# SolarPanel_2p2AZ1.net
KiCad netlist of a schematic drawn in EAGLE
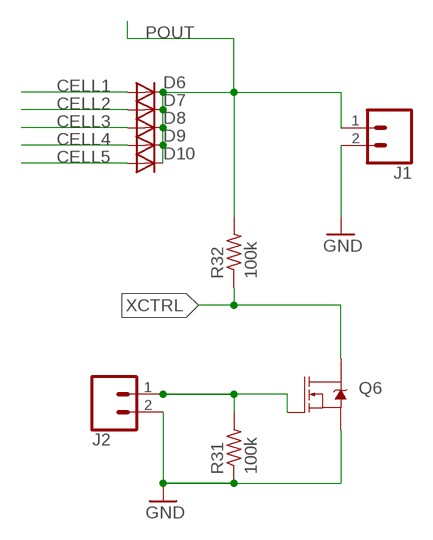
[diagram p0: schematic, sheet 1]
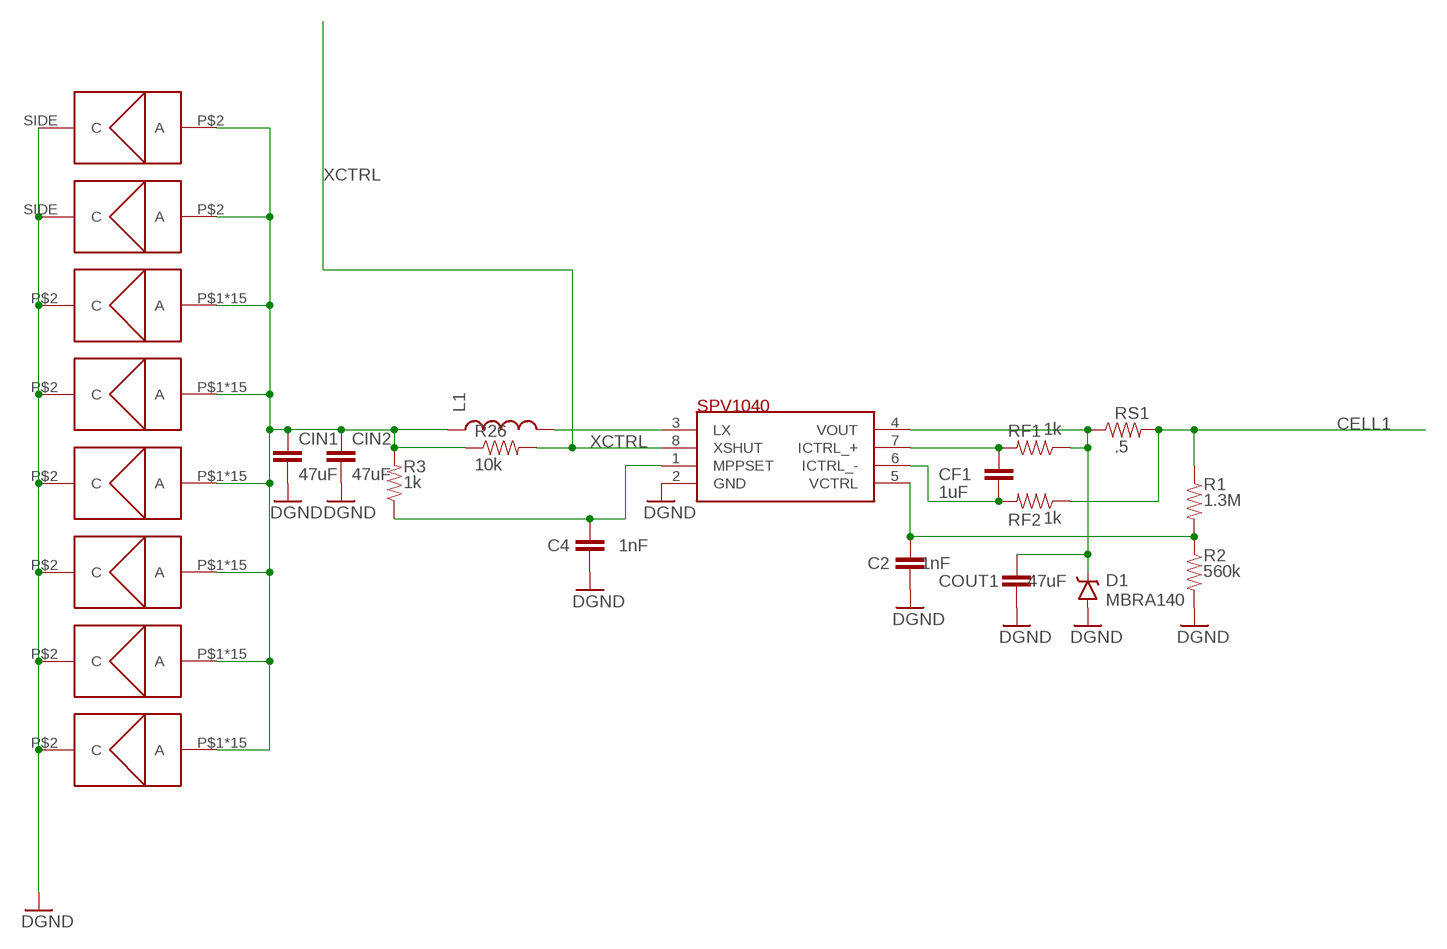
[diagram p1: schematic, sheet 2]
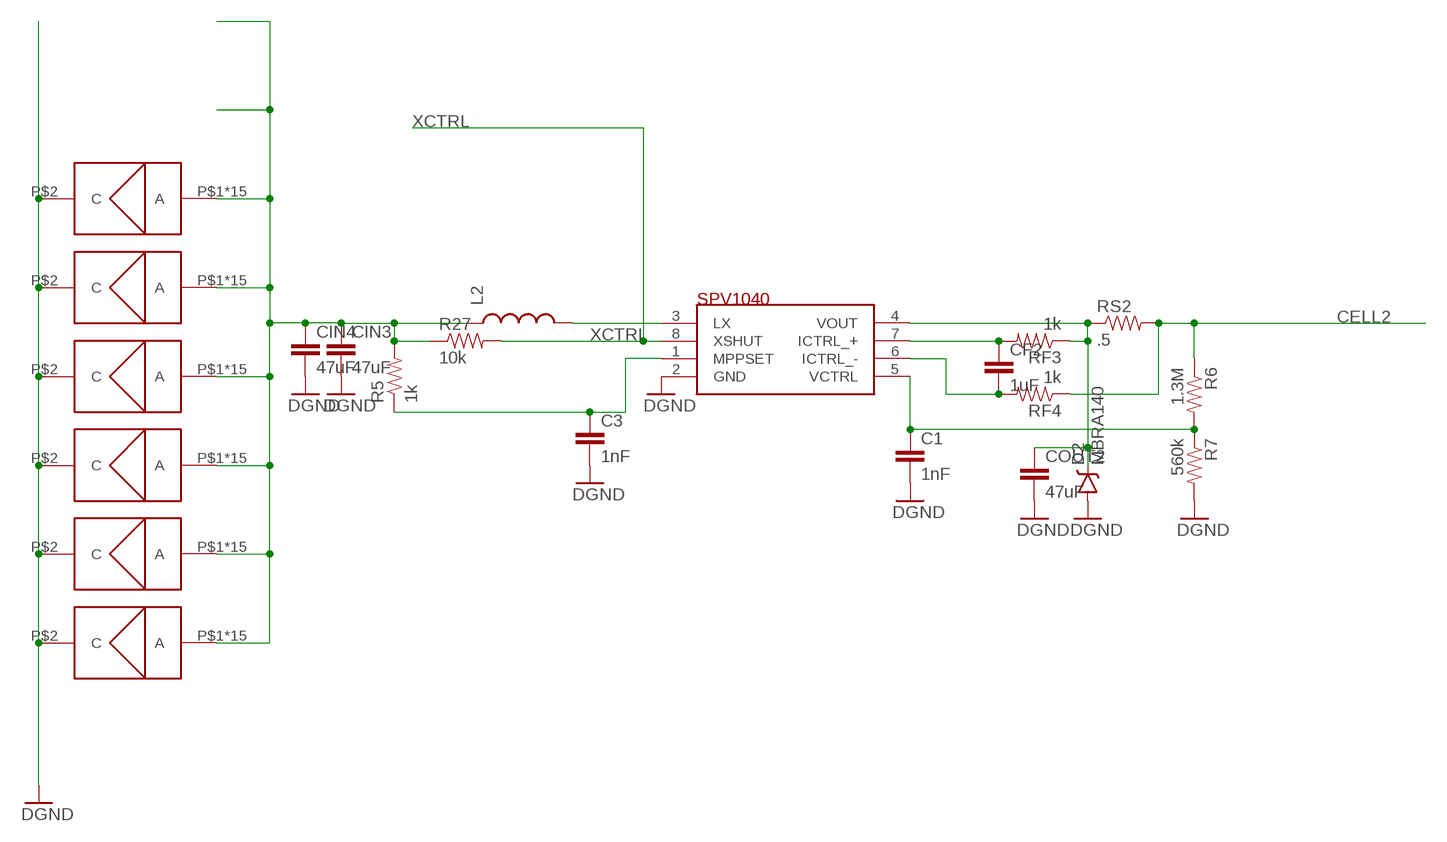
[diagram p2: schematic, sheet 3]
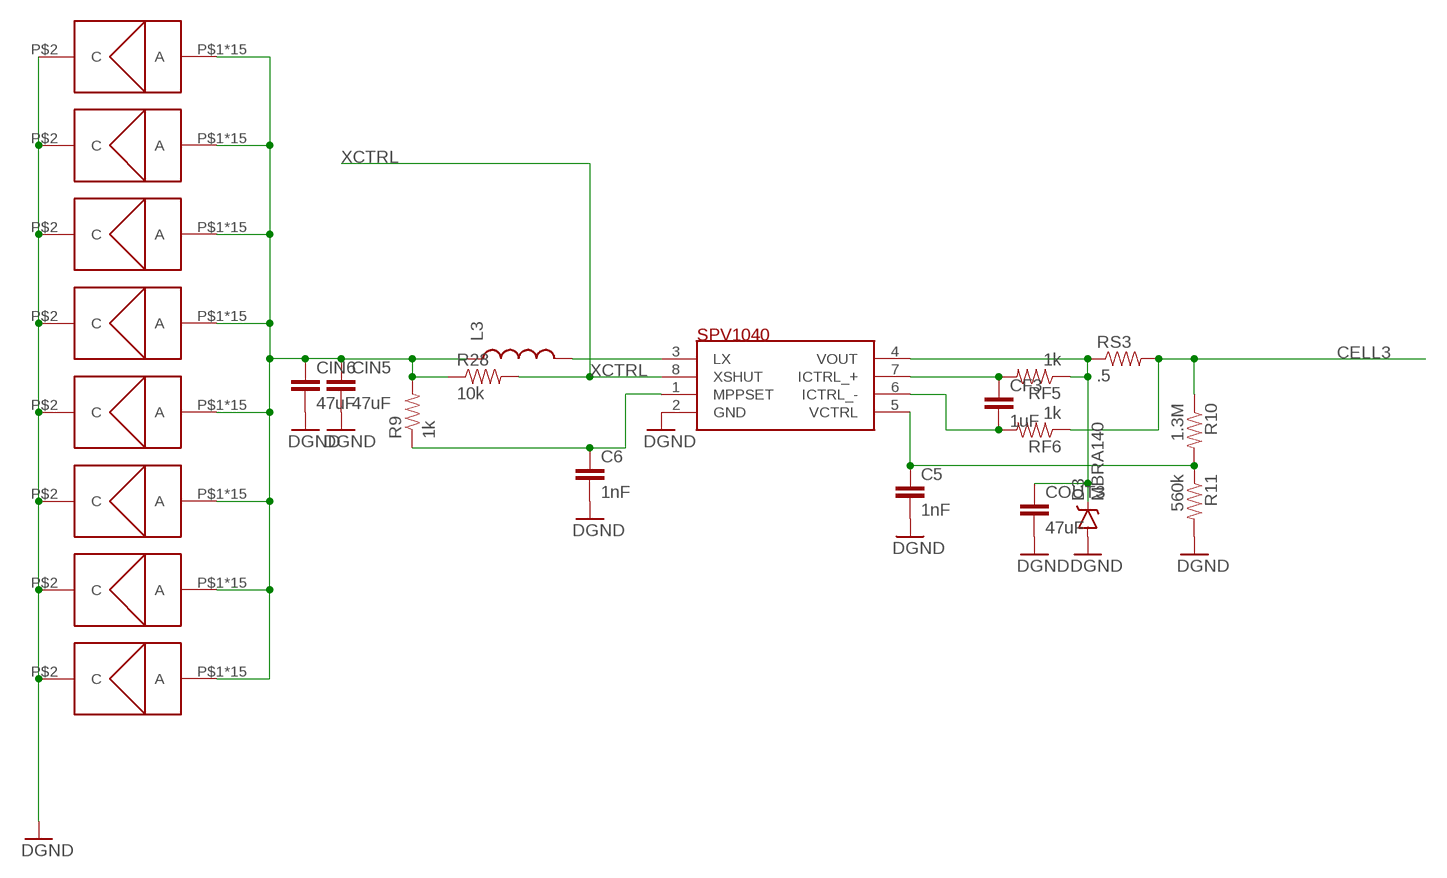
[diagram p3: schematic, sheet 4]
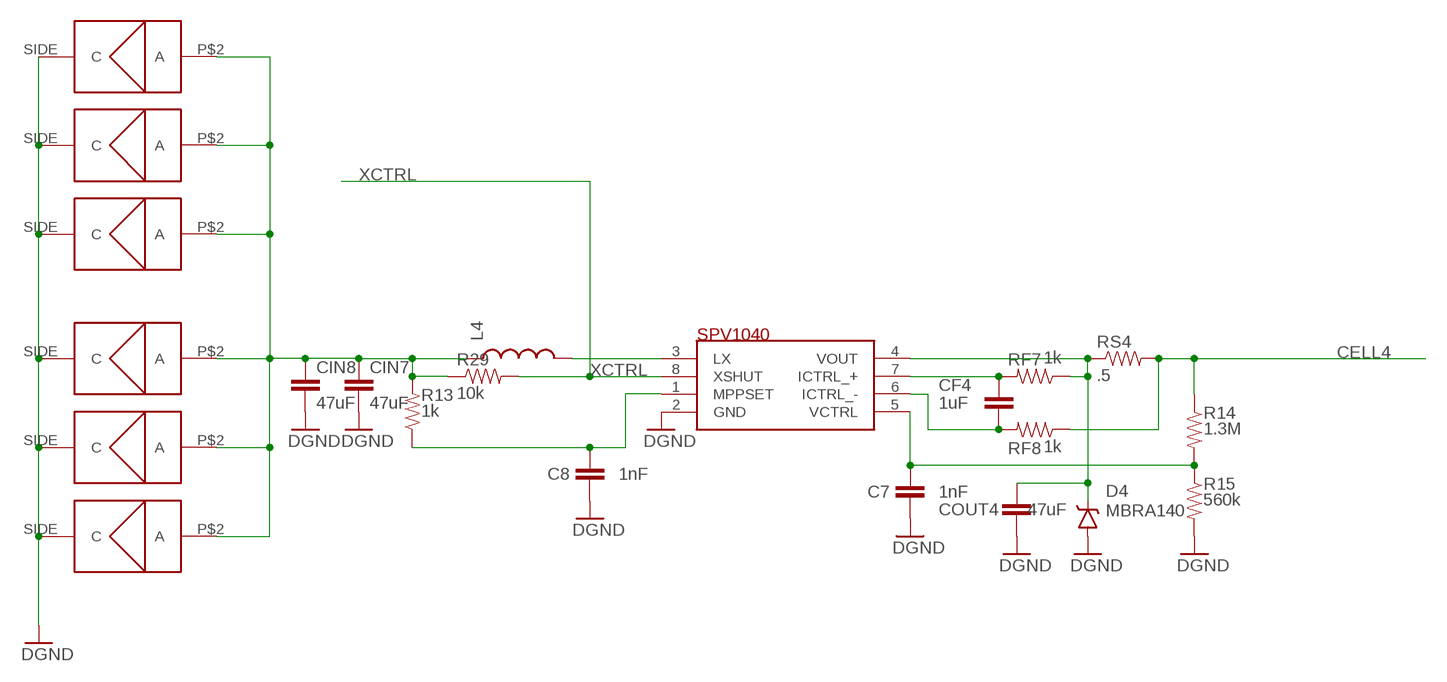
[diagram p4: schematic, sheet 5]
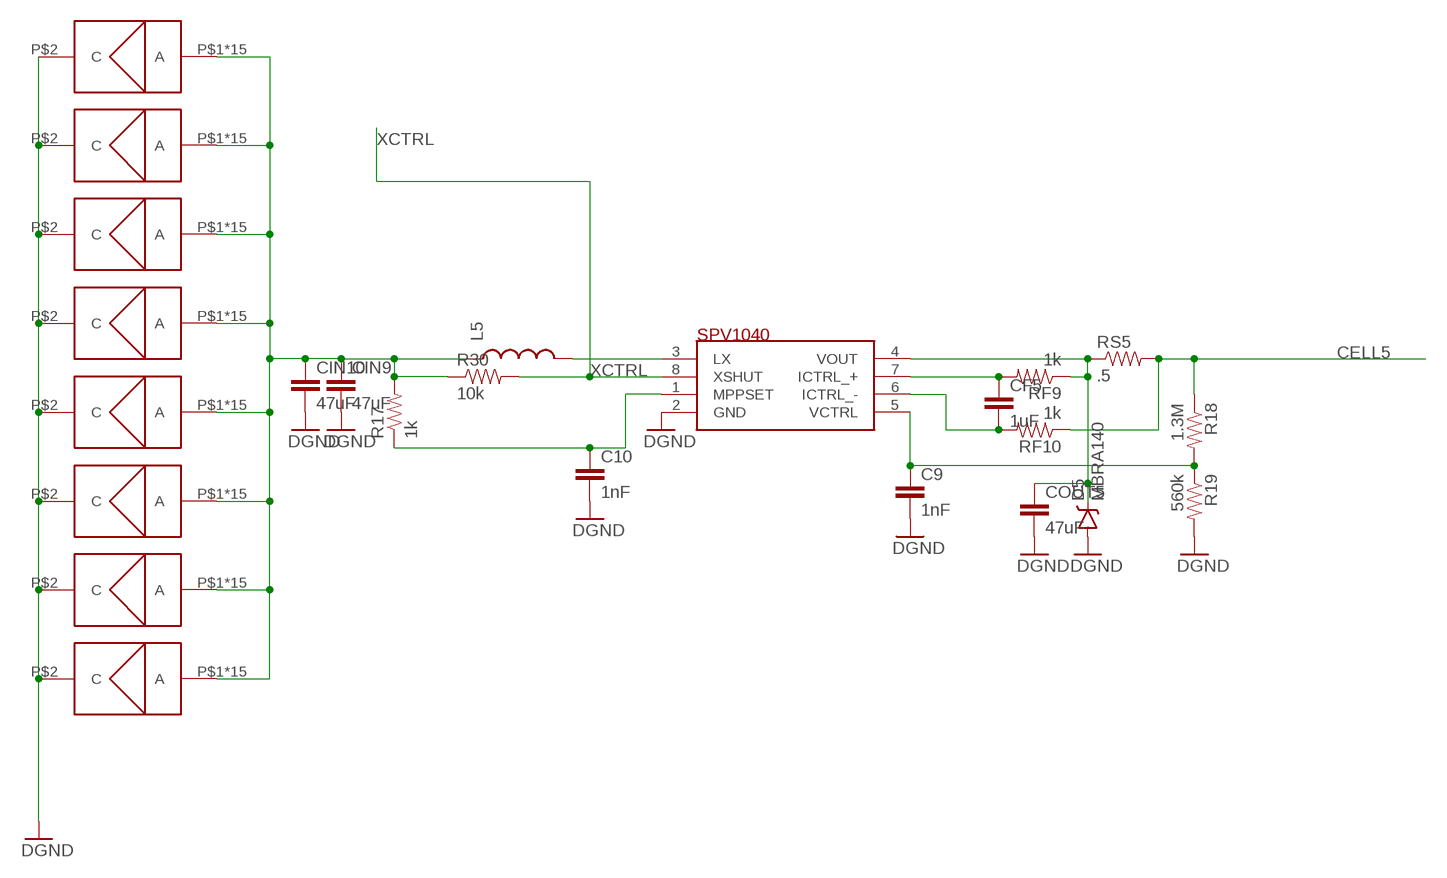
[diagram p5: schematic, sheet 6]

(export (version "E")
  (design (tool "Eeschema 10.0.6"))
  (components
    (comp (ref "C2")
      (value "1nF")
      (footprint "eagle-import:0603-CAP")
      (libsource (lib "eagle-import") (part "CAP0603-CAP"))
    )
    (comp (ref "C4")
      (value "1nF")
      (footprint "eagle-import:0603-CAP")
      (libsource (lib "eagle-import") (part "CAP0603-CAP"))
    )
    (comp (ref "CF1")
      (value "1uF")
      (footprint "eagle-import:0603-CAP")
      (libsource (lib "eagle-import") (part "CAP0603-CAP"))
    )
    (comp (ref "CIN1")
      (value "47uF")
      (footprint "eagle-import:1206")
      (libsource (lib "eagle-import") (part "CAP1206"))
    )
    (comp (ref "CIN2")
      (value "47uF")
      (footprint "eagle-import:1206")
      (libsource (lib "eagle-import") (part "CAP1206"))
    )
    (comp (ref "COUT1")
      (value "47uF")
      (footprint "eagle-import:1206")
      (libsource (lib "eagle-import") (part "CAP1206"))
    )
    (comp (ref "D1")
      (value "MBRA140")
      (footprint "eagle-import:SMA-DIODE")
      (libsource (lib "eagle-import") (part "DIODE-SCHOTTKY-MBRA140"))
    )
    (comp (ref "L1")
      (value "INDUCTOR1210")
      (footprint "eagle-import:1210")
      (libsource (lib "eagle-import") (part "INDUCTOR1210"))
    )
    (comp (ref "R1")
      (value "1.3M")
      (footprint "eagle-import:0603-RES")
      (libsource (lib "eagle-import") (part "RESISTOR0603-RES"))
    )
    (comp (ref "R2")
      (value "560k")
      (footprint "eagle-import:0603-RES")
      (libsource (lib "eagle-import") (part "RESISTOR0603-RES"))
    )
    (comp (ref "R3")
      (value "1k")
      (footprint "eagle-import:0603-RES")
      (libsource (lib "eagle-import") (part "RESISTOR0603-RES"))
    )
    (comp (ref "R26")
      (value "10k")
      (footprint "eagle-import:0603-RES")
      (libsource (lib "eagle-import") (part "RESISTOR0603-RES"))
    )
    (comp (ref "RF1")
      (value "1k")
      (footprint "eagle-import:0603-RES")
      (libsource (lib "eagle-import") (part "RESISTOR0603-RES"))
    )
    (comp (ref "RF2")
      (value "1k")
      (footprint "eagle-import:0603-RES")
      (libsource (lib "eagle-import") (part "RESISTOR0603-RES"))
    )
    (comp (ref "RS1")
      (value ".5")
      (footprint "eagle-import:0603-RES")
      (libsource (lib "eagle-import") (part "RESISTOR0603-RES"))
    )
    (comp (ref "U$11")
      (value "TASC_VIA")
      (footprint "eagle-import:TASC_VIA")
      (libsource (lib "eagle-import") (part "TASC_VIA"))
    )
    (comp (ref "U$12")
      (value "TASC_VIA")
      (footprint "eagle-import:TASC_VIA")
      (libsource (lib "eagle-import") (part "TASC_VIA"))
    )
    (comp (ref "U$13")
      (value "TASC_VIA")
      (footprint "eagle-import:TASC_VIA")
      (libsource (lib "eagle-import") (part "TASC_VIA"))
    )
    (comp (ref "U$14")
      (value "TASC_VIA")
      (footprint "eagle-import:TASC_VIA")
      (libsource (lib "eagle-import") (part "TASC_VIA"))
    )
    (comp (ref "U$15")
      (value "SPV1040")
      (footprint "eagle-import:TSSOP8")
      (libsource (lib "eagle-import") (part "SPV1040"))
    )
    (comp (ref "U$16")
      (value "TASC_VIA")
      (footprint "eagle-import:TASC_VIA")
      (libsource (lib "eagle-import") (part "TASC_VIA"))
    )
    (comp (ref "U$17")
      (value "TASC_VIA")
      (footprint "eagle-import:TASC_VIA")
      (libsource (lib "eagle-import") (part "TASC_VIA"))
    )
    (comp (ref "U$18")
      (value "TASC")
      (footprint "eagle-import:TASC")
      (libsource (lib "eagle-import") (part "TASC"))
    )
    (comp (ref "U$19")
      (value "TASC")
      (footprint "eagle-import:TASC")
      (libsource (lib "eagle-import") (part "TASC"))
    )
    (comp (ref "C1")
      (value "1nF")
      (footprint "eagle-import:0603-CAP")
      (libsource (lib "eagle-import") (part "CAP0603-CAP"))
    )
    (comp (ref "C3")
      (value "1nF")
      (footprint "eagle-import:0603-CAP")
      (libsource (lib "eagle-import") (part "CAP0603-CAP"))
    )
    (comp (ref "CF2")
      (value "1uF")
      (footprint "eagle-import:0603-CAP")
      (libsource (lib "eagle-import") (part "CAP0603-CAP"))
    )
    (comp (ref "CIN3")
      (value "47uF")
      (footprint "eagle-import:1206")
      (libsource (lib "eagle-import") (part "CAP1206"))
    )
    (comp (ref "CIN4")
      (value "47uF")
      (footprint "eagle-import:1206")
      (libsource (lib "eagle-import") (part "CAP1206"))
    )
    (comp (ref "COUT2")
      (value "47uF")
      (footprint "eagle-import:1206")
      (libsource (lib "eagle-import") (part "CAP1206"))
    )
    (comp (ref "D2")
      (value "MBRA140")
      (footprint "eagle-import:SMA-DIODE")
      (libsource (lib "eagle-import") (part "DIODE-SCHOTTKY-MBRA140"))
    )
    (comp (ref "L2")
      (value "INDUCTOR1210")
      (footprint "eagle-import:1210")
      (libsource (lib "eagle-import") (part "INDUCTOR1210"))
    )
    (comp (ref "R5")
      (value "1k")
      (footprint "eagle-import:0603-RES")
      (libsource (lib "eagle-import") (part "RESISTOR0603-RES"))
    )
    (comp (ref "R6")
      (value "1.3M")
      (footprint "eagle-import:0603-RES")
      (libsource (lib "eagle-import") (part "RESISTOR0603-RES"))
    )
    (comp (ref "R7")
      (value "560k")
      (footprint "eagle-import:0603-RES")
      (libsource (lib "eagle-import") (part "RESISTOR0603-RES"))
    )
    (comp (ref "R27")
      (value "10k")
      (footprint "eagle-import:0603-RES")
      (libsource (lib "eagle-import") (part "RESISTOR0603-RES"))
    )
    (comp (ref "RF3")
      (value "1k")
      (footprint "eagle-import:0603-RES")
      (libsource (lib "eagle-import") (part "RESISTOR0603-RES"))
    )
    (comp (ref "RF4")
      (value "1k")
      (footprint "eagle-import:0603-RES")
      (libsource (lib "eagle-import") (part "RESISTOR0603-RES"))
    )
    (comp (ref "RS2")
      (value ".5")
      (footprint "eagle-import:0603-RES")
      (libsource (lib "eagle-import") (part "RESISTOR0603-RES"))
    )
    (comp (ref "U$1")
      (value "TASC_VIA")
      (footprint "eagle-import:TASC_VIA")
      (libsource (lib "eagle-import") (part "TASC_VIA"))
    )
    (comp (ref "U$2")
      (value "TASC_VIA")
      (footprint "eagle-import:TASC_VIA")
      (libsource (lib "eagle-import") (part "TASC_VIA"))
    )
    (comp (ref "U$3")
      (value "TASC_VIA")
      (footprint "eagle-import:TASC_VIA")
      (libsource (lib "eagle-import") (part "TASC_VIA"))
    )
    (comp (ref "U$4")
      (value "TASC_VIA")
      (footprint "eagle-import:TASC_VIA")
      (libsource (lib "eagle-import") (part "TASC_VIA"))
    )
    (comp (ref "U$5")
      (value "SPV1040")
      (footprint "eagle-import:TSSOP8")
      (libsource (lib "eagle-import") (part "SPV1040"))
    )
    (comp (ref "U$6")
      (value "TASC_VIA")
      (footprint "eagle-import:TASC_VIA")
      (libsource (lib "eagle-import") (part "TASC_VIA"))
    )
    (comp (ref "U$7")
      (value "TASC_VIA")
      (footprint "eagle-import:TASC_VIA")
      (libsource (lib "eagle-import") (part "TASC_VIA"))
    )
    (comp (ref "C5")
      (value "1nF")
      (footprint "eagle-import:0603-CAP")
      (libsource (lib "eagle-import") (part "CAP0603-CAP"))
    )
    (comp (ref "C6")
      (value "1nF")
      (footprint "eagle-import:0603-CAP")
      (libsource (lib "eagle-import") (part "CAP0603-CAP"))
    )
    (comp (ref "CF3")
      (value "1uF")
      (footprint "eagle-import:0603-CAP")
      (libsource (lib "eagle-import") (part "CAP0603-CAP"))
    )
    (comp (ref "CIN5")
      (value "47uF")
      (footprint "eagle-import:1206")
      (libsource (lib "eagle-import") (part "CAP1206"))
    )
    (comp (ref "CIN6")
      (value "47uF")
      (footprint "eagle-import:1206")
      (libsource (lib "eagle-import") (part "CAP1206"))
    )
    (comp (ref "COUT3")
      (value "47uF")
      (footprint "eagle-import:1206")
      (libsource (lib "eagle-import") (part "CAP1206"))
    )
    (comp (ref "D3")
      (value "MBRA140")
      (footprint "eagle-import:SMA-DIODE")
      (libsource (lib "eagle-import") (part "DIODE-SCHOTTKY-MBRA140"))
    )
    (comp (ref "L3")
      (value "INDUCTOR1210")
      (footprint "eagle-import:1210")
      (libsource (lib "eagle-import") (part "INDUCTOR1210"))
    )
    (comp (ref "R9")
      (value "1k")
      (footprint "eagle-import:0603-RES")
      (libsource (lib "eagle-import") (part "RESISTOR0603-RES"))
    )
    (comp (ref "R10")
      (value "1.3M")
      (footprint "eagle-import:0603-RES")
      (libsource (lib "eagle-import") (part "RESISTOR0603-RES"))
    )
    (comp (ref "R11")
      (value "560k")
      (footprint "eagle-import:0603-RES")
      (libsource (lib "eagle-import") (part "RESISTOR0603-RES"))
    )
    (comp (ref "R28")
      (value "10k")
      (footprint "eagle-import:0603-RES")
      (libsource (lib "eagle-import") (part "RESISTOR0603-RES"))
    )
    (comp (ref "RF5")
      (value "1k")
      (footprint "eagle-import:0603-RES")
      (libsource (lib "eagle-import") (part "RESISTOR0603-RES"))
    )
    (comp (ref "RF6")
      (value "1k")
      (footprint "eagle-import:0603-RES")
      (libsource (lib "eagle-import") (part "RESISTOR0603-RES"))
    )
    (comp (ref "RS3")
      (value ".5")
      (footprint "eagle-import:0603-RES")
      (libsource (lib "eagle-import") (part "RESISTOR0603-RES"))
    )
    (comp (ref "U$21")
      (value "TASC_VIA")
      (footprint "eagle-import:TASC_VIA")
      (libsource (lib "eagle-import") (part "TASC_VIA"))
    )
    (comp (ref "U$22")
      (value "TASC_VIA")
      (footprint "eagle-import:TASC_VIA")
      (libsource (lib "eagle-import") (part "TASC_VIA"))
    )
    (comp (ref "U$23")
      (value "TASC_VIA")
      (footprint "eagle-import:TASC_VIA")
      (libsource (lib "eagle-import") (part "TASC_VIA"))
    )
    (comp (ref "U$24")
      (value "TASC_VIA")
      (footprint "eagle-import:TASC_VIA")
      (libsource (lib "eagle-import") (part "TASC_VIA"))
    )
    (comp (ref "U$25")
      (value "SPV1040")
      (footprint "eagle-import:TSSOP8")
      (libsource (lib "eagle-import") (part "SPV1040"))
    )
    (comp (ref "U$26")
      (value "TASC_VIA")
      (footprint "eagle-import:TASC_VIA")
      (libsource (lib "eagle-import") (part "TASC_VIA"))
    )
    (comp (ref "U$27")
      (value "TASC_VIA")
      (footprint "eagle-import:TASC_VIA")
      (libsource (lib "eagle-import") (part "TASC_VIA"))
    )
    (comp (ref "U$28")
      (value "TASC_VIA")
      (footprint "eagle-import:TASC_VIA")
      (libsource (lib "eagle-import") (part "TASC_VIA"))
    )
    (comp (ref "U$29")
      (value "TASC_VIA")
      (footprint "eagle-import:TASC_VIA")
      (libsource (lib "eagle-import") (part "TASC_VIA"))
    )
    (comp (ref "D6")
      (value "DIODE-SOD123")
      (footprint "eagle-import:SOD123")
      (libsource (lib "eagle-import") (part "DIODE-SOD123"))
    )
    (comp (ref "D7")
      (value "DIODE-SOD123")
      (footprint "eagle-import:SOD123")
      (libsource (lib "eagle-import") (part "DIODE-SOD123"))
    )
    (comp (ref "D8")
      (value "DIODE-SOD123")
      (footprint "eagle-import:SOD123")
      (libsource (lib "eagle-import") (part "DIODE-SOD123"))
    )
    (comp (ref "D9")
      (value "DIODE-SOD123")
      (footprint "eagle-import:SOD123")
      (libsource (lib "eagle-import") (part "DIODE-SOD123"))
    )
    (comp (ref "D10")
      (value "DIODE-SOD123")
      (footprint "eagle-import:SOD123")
      (libsource (lib "eagle-import") (part "DIODE-SOD123"))
    )
    (comp (ref "J1")
      (value "CONN_02")
      (footprint "eagle-import:1X02")
      (libsource (lib "eagle-import") (part "CONN_02"))
    )
    (comp (ref "J2")
      (value "CONN_02")
      (footprint "eagle-import:1X02")
      (libsource (lib "eagle-import") (part "CONN_02"))
    )
    (comp (ref "Q6")
      (value "MOSFET-NCH-BSS138")
      (footprint "eagle-import:SOT23-3")
      (libsource (lib "eagle-import") (part "MOSFET-NCH-BSS138"))
    )
    (comp (ref "R31")
      (value "100k")
      (footprint "eagle-import:R0603")
      (libsource (lib "eagle-import") (part "R-US_R0603"))
    )
    (comp (ref "R32")
      (value "100k")
      (footprint "eagle-import:R0603")
      (libsource (lib "eagle-import") (part "R-US_R0603"))
    )
    (comp (ref "C7")
      (value "1nF")
      (footprint "eagle-import:0603-CAP")
      (libsource (lib "eagle-import") (part "CAP0603-CAP"))
    )
    (comp (ref "C8")
      (value "1nF")
      (footprint "eagle-import:0603-CAP")
      (libsource (lib "eagle-import") (part "CAP0603-CAP"))
    )
    (comp (ref "CF4")
      (value "1uF")
      (footprint "eagle-import:0603-CAP")
      (libsource (lib "eagle-import") (part "CAP0603-CAP"))
    )
    (comp (ref "CIN7")
      (value "47uF")
      (footprint "eagle-import:1206")
      (libsource (lib "eagle-import") (part "CAP1206"))
    )
    (comp (ref "CIN8")
      (value "47uF")
      (footprint "eagle-import:1206")
      (libsource (lib "eagle-import") (part "CAP1206"))
    )
    (comp (ref "COUT4")
      (value "47uF")
      (footprint "eagle-import:1206")
      (libsource (lib "eagle-import") (part "CAP1206"))
    )
    (comp (ref "D4")
      (value "MBRA140")
      (footprint "eagle-import:SMA-DIODE")
      (libsource (lib "eagle-import") (part "DIODE-SCHOTTKY-MBRA140"))
    )
    (comp (ref "L4")
      (value "INDUCTOR1210")
      (footprint "eagle-import:1210")
      (libsource (lib "eagle-import") (part "INDUCTOR1210"))
    )
    (comp (ref "R13")
      (value "1k")
      (footprint "eagle-import:0603-RES")
      (libsource (lib "eagle-import") (part "RESISTOR0603-RES"))
    )
    (comp (ref "R14")
      (value "1.3M")
      (footprint "eagle-import:0603-RES")
      (libsource (lib "eagle-import") (part "RESISTOR0603-RES"))
    )
    (comp (ref "R15")
      (value "560k")
      (footprint "eagle-import:0603-RES")
      (libsource (lib "eagle-import") (part "RESISTOR0603-RES"))
    )
    (comp (ref "R29")
      (value "10k")
      (footprint "eagle-import:0603-RES")
      (libsource (lib "eagle-import") (part "RESISTOR0603-RES"))
    )
    (comp (ref "RF7")
      (value "1k")
      (footprint "eagle-import:0603-RES")
      (libsource (lib "eagle-import") (part "RESISTOR0603-RES"))
    )
    (comp (ref "RF8")
      (value "1k")
      (footprint "eagle-import:0603-RES")
      (libsource (lib "eagle-import") (part "RESISTOR0603-RES"))
    )
    (comp (ref "RS4")
      (value ".5")
      (footprint "eagle-import:0603-RES")
      (libsource (lib "eagle-import") (part "RESISTOR0603-RES"))
    )
    (comp (ref "U$33")
      (value "TASC")
      (footprint "eagle-import:TASC")
      (libsource (lib "eagle-import") (part "TASC"))
    )
    (comp (ref "U$34")
      (value "TASC")
      (footprint "eagle-import:TASC")
      (libsource (lib "eagle-import") (part "TASC"))
    )
    (comp (ref "U$35")
      (value "SPV1040")
      (footprint "eagle-import:TSSOP8")
      (libsource (lib "eagle-import") (part "SPV1040"))
    )
    (comp (ref "U$36")
      (value "TASC")
      (footprint "eagle-import:TASC")
      (libsource (lib "eagle-import") (part "TASC"))
    )
    (comp (ref "U$37")
      (value "TASC")
      (footprint "eagle-import:TASC")
      (libsource (lib "eagle-import") (part "TASC"))
    )
    (comp (ref "U$38")
      (value "TASC")
      (footprint "eagle-import:TASC")
      (libsource (lib "eagle-import") (part "TASC"))
    )
    (comp (ref "U$39")
      (value "TASC")
      (footprint "eagle-import:TASC")
      (libsource (lib "eagle-import") (part "TASC"))
    )
    (comp (ref "C9")
      (value "1nF")
      (footprint "eagle-import:0603-CAP")
      (libsource (lib "eagle-import") (part "CAP0603-CAP"))
    )
    (comp (ref "C10")
      (value "1nF")
      (footprint "eagle-import:0603-CAP")
      (libsource (lib "eagle-import") (part "CAP0603-CAP"))
    )
    (comp (ref "CF5")
      (value "1uF")
      (footprint "eagle-import:0603-CAP")
      (libsource (lib "eagle-import") (part "CAP0603-CAP"))
    )
    (comp (ref "CIN9")
      (value "47uF")
      (footprint "eagle-import:1206")
      (libsource (lib "eagle-import") (part "CAP1206"))
    )
    (comp (ref "CIN10")
      (value "47uF")
      (footprint "eagle-import:1206")
      (libsource (lib "eagle-import") (part "CAP1206"))
    )
    (comp (ref "COUT5")
      (value "47uF")
      (footprint "eagle-import:1206")
      (libsource (lib "eagle-import") (part "CAP1206"))
    )
    (comp (ref "D5")
      (value "MBRA140")
      (footprint "eagle-import:SMA-DIODE")
      (libsource (lib "eagle-import") (part "DIODE-SCHOTTKY-MBRA140"))
    )
    (comp (ref "L5")
      (value "INDUCTOR1210")
      (footprint "eagle-import:1210")
      (libsource (lib "eagle-import") (part "INDUCTOR1210"))
    )
    (comp (ref "R17")
      (value "1k")
      (footprint "eagle-import:0603-RES")
      (libsource (lib "eagle-import") (part "RESISTOR0603-RES"))
    )
    (comp (ref "R18")
      (value "1.3M")
      (footprint "eagle-import:0603-RES")
      (libsource (lib "eagle-import") (part "RESISTOR0603-RES"))
    )
    (comp (ref "R19")
      (value "560k")
      (footprint "eagle-import:0603-RES")
      (libsource (lib "eagle-import") (part "RESISTOR0603-RES"))
    )
    (comp (ref "R30")
      (value "10k")
      (footprint "eagle-import:0603-RES")
      (libsource (lib "eagle-import") (part "RESISTOR0603-RES"))
    )
    (comp (ref "RF9")
      (value "1k")
      (footprint "eagle-import:0603-RES")
      (libsource (lib "eagle-import") (part "RESISTOR0603-RES"))
    )
    (comp (ref "RF10")
      (value "1k")
      (footprint "eagle-import:0603-RES")
      (libsource (lib "eagle-import") (part "RESISTOR0603-RES"))
    )
    (comp (ref "RS5")
      (value ".5")
      (footprint "eagle-import:0603-RES")
      (libsource (lib "eagle-import") (part "RESISTOR0603-RES"))
    )
    (comp (ref "U$41")
      (value "TASC_VIA")
      (footprint "eagle-import:TASC_VIA")
      (libsource (lib "eagle-import") (part "TASC_VIA"))
    )
    (comp (ref "U$42")
      (value "TASC_VIA")
      (footprint "eagle-import:TASC_VIA")
      (libsource (lib "eagle-import") (part "TASC_VIA"))
    )
    (comp (ref "U$43")
      (value "TASC_VIA")
      (footprint "eagle-import:TASC_VIA")
      (libsource (lib "eagle-import") (part "TASC_VIA"))
    )
    (comp (ref "U$44")
      (value "TASC_VIA")
      (footprint "eagle-import:TASC_VIA")
      (libsource (lib "eagle-import") (part "TASC_VIA"))
    )
    (comp (ref "U$45")
      (value "SPV1040")
      (footprint "eagle-import:TSSOP8")
      (libsource (lib "eagle-import") (part "SPV1040"))
    )
    (comp (ref "U$46")
      (value "TASC_VIA")
      (footprint "eagle-import:TASC_VIA")
      (libsource (lib "eagle-import") (part "TASC_VIA"))
    )
    (comp (ref "U$47")
      (value "TASC_VIA")
      (footprint "eagle-import:TASC_VIA")
      (libsource (lib "eagle-import") (part "TASC_VIA"))
    )
    (comp (ref "U$48")
      (value "TASC_VIA")
      (footprint "eagle-import:TASC_VIA")
      (libsource (lib "eagle-import") (part "TASC_VIA"))
    )
    (comp (ref "U$49")
      (value "TASC_VIA")
      (footprint "eagle-import:TASC_VIA")
      (libsource (lib "eagle-import") (part "TASC_VIA"))
    )
  )
  (nets
    (net (code "1") (name "CELL1") (class "Default")
      (node (ref "D6") (pin "A") (pinfunction "A_A") (pintype "passive"))
      (node (ref "R1") (pin "1") (pinfunction "1_1") (pintype "passive"))
      (node (ref "RF2") (pin "1") (pinfunction "1_1") (pintype "passive"))
      (node (ref "RS1") (pin "2") (pinfunction "2_2") (pintype "passive"))
    )
    (net (code "2") (name "CELL2") (class "Default")
      (node (ref "D7") (pin "A") (pinfunction "A_A") (pintype "passive"))
      (node (ref "R6") (pin "1") (pinfunction "1_1") (pintype "passive"))
      (node (ref "RF4") (pin "1") (pinfunction "1_1") (pintype "passive"))
      (node (ref "RS2") (pin "2") (pinfunction "2_2") (pintype "passive"))
    )
    (net (code "3") (name "CELL3") (class "Default")
      (node (ref "D8") (pin "A") (pinfunction "A_A") (pintype "passive"))
      (node (ref "R10") (pin "1") (pinfunction "1_1") (pintype "passive"))
      (node (ref "RF6") (pin "1") (pinfunction "1_1") (pintype "passive"))
      (node (ref "RS3") (pin "2") (pinfunction "2_2") (pintype "passive"))
    )
    (net (code "4") (name "CELL4") (class "Default")
      (node (ref "D9") (pin "A") (pinfunction "A_A") (pintype "passive"))
      (node (ref "R14") (pin "1") (pinfunction "1_1") (pintype "passive"))
      (node (ref "RF8") (pin "1") (pinfunction "1_1") (pintype "passive"))
      (node (ref "RS4") (pin "2") (pinfunction "2_2") (pintype "passive"))
    )
    (net (code "5") (name "CELL5") (class "Default")
      (node (ref "D10") (pin "A") (pinfunction "A_A") (pintype "passive"))
      (node (ref "R18") (pin "1") (pinfunction "1_1") (pintype "passive"))
      (node (ref "RF10") (pin "1") (pinfunction "1_1") (pintype "passive"))
      (node (ref "RS5") (pin "2") (pinfunction "2_2") (pintype "passive"))
    )
    (net (code "6") (name "GND") (class "Default")
      (node (ref "C1") (pin "2") (pinfunction "2_2") (pintype "passive"))
      (node (ref "C10") (pin "2") (pinfunction "2_2") (pintype "passive"))
      (node (ref "C2") (pin "2") (pinfunction "2_2") (pintype "passive"))
      (node (ref "C3") (pin "2") (pinfunction "2_2") (pintype "passive"))
      (node (ref "C4") (pin "2") (pinfunction "2_2") (pintype "passive"))
      (node (ref "C5") (pin "2") (pinfunction "2_2") (pintype "passive"))
      (node (ref "C6") (pin "2") (pinfunction "2_2") (pintype "passive"))
      (node (ref "C7") (pin "2") (pinfunction "2_2") (pintype "passive"))
      (node (ref "C8") (pin "2") (pinfunction "2_2") (pintype "passive"))
      (node (ref "C9") (pin "2") (pinfunction "2_2") (pintype "passive"))
      (node (ref "CIN1") (pin "2") (pinfunction "2_2") (pintype "passive"))
      (node (ref "CIN10") (pin "2") (pinfunction "2_2") (pintype "passive"))
      (node (ref "CIN2") (pin "2") (pinfunction "2_2") (pintype "passive"))
      (node (ref "CIN3") (pin "2") (pinfunction "2_2") (pintype "passive"))
      (node (ref "CIN4") (pin "2") (pinfunction "2_2") (pintype "passive"))
      (node (ref "CIN5") (pin "2") (pinfunction "2_2") (pintype "passive"))
      (node (ref "CIN6") (pin "2") (pinfunction "2_2") (pintype "passive"))
      (node (ref "CIN7") (pin "2") (pinfunction "2_2") (pintype "passive"))
      (node (ref "CIN8") (pin "2") (pinfunction "2_2") (pintype "passive"))
      (node (ref "CIN9") (pin "2") (pinfunction "2_2") (pintype "passive"))
      (node (ref "COUT1") (pin "2") (pinfunction "2_2") (pintype "passive"))
      (node (ref "COUT2") (pin "2") (pinfunction "2_2") (pintype "passive"))
      (node (ref "COUT3") (pin "2") (pinfunction "2_2") (pintype "passive"))
      (node (ref "COUT4") (pin "2") (pinfunction "2_2") (pintype "passive"))
      (node (ref "COUT5") (pin "2") (pinfunction "2_2") (pintype "passive"))
      (node (ref "D1") (pin "A") (pinfunction "A_A") (pintype "passive"))
      (node (ref "D2") (pin "A") (pinfunction "A_A") (pintype "passive"))
      (node (ref "D3") (pin "A") (pinfunction "A_A") (pintype "passive"))
      (node (ref "D4") (pin "A") (pinfunction "A_A") (pintype "passive"))
      (node (ref "D5") (pin "A") (pinfunction "A_A") (pintype "passive"))
      (node (ref "J1") (pin "2") (pinfunction "2_2") (pintype "passive"))
      (node (ref "J2") (pin "2") (pinfunction "2_2") (pintype "passive"))
      (node (ref "Q6") (pin "2") (pinfunction "S_2") (pintype "bidirectional"))
      (node (ref "R11") (pin "2") (pinfunction "2_2") (pintype "passive"))
      (node (ref "R15") (pin "2") (pinfunction "2_2") (pintype "passive"))
      (node (ref "R19") (pin "2") (pinfunction "2_2") (pintype "passive"))
      (node (ref "R2") (pin "2") (pinfunction "2_2") (pintype "passive"))
      (node (ref "R31") (pin "1") (pinfunction "1_1") (pintype "passive"))
      (node (ref "R7") (pin "2") (pinfunction "2_2") (pintype "passive"))
      (node (ref "U$1") (pin "P$2") (pinfunction "C_P$2") (pintype "bidirectional"))
      (node (ref "U$11") (pin "P$2") (pinfunction "C_P$2") (pintype "bidirectional"))
      (node (ref "U$12") (pin "P$2") (pinfunction "C_P$2") (pintype "bidirectional"))
      (node (ref "U$13") (pin "P$2") (pinfunction "C_P$2") (pintype "bidirectional"))
      (node (ref "U$14") (pin "P$2") (pinfunction "C_P$2") (pintype "bidirectional"))
      (node (ref "U$15") (pin "2") (pinfunction "GND_2") (pintype "bidirectional"))
      (node (ref "U$16") (pin "P$2") (pinfunction "C_P$2") (pintype "bidirectional"))
      (node (ref "U$17") (pin "P$2") (pinfunction "C_P$2") (pintype "bidirectional"))
      (node (ref "U$18") (pin "SIDE") (pinfunction "C_SIDE") (pintype "bidirectional"))
      (node (ref "U$19") (pin "SIDE") (pinfunction "C_SIDE") (pintype "bidirectional"))
      (node (ref "U$2") (pin "P$2") (pinfunction "C_P$2") (pintype "bidirectional"))
      (node (ref "U$21") (pin "P$2") (pinfunction "C_P$2") (pintype "bidirectional"))
      (node (ref "U$22") (pin "P$2") (pinfunction "C_P$2") (pintype "bidirectional"))
      (node (ref "U$23") (pin "P$2") (pinfunction "C_P$2") (pintype "bidirectional"))
      (node (ref "U$24") (pin "P$2") (pinfunction "C_P$2") (pintype "bidirectional"))
      (node (ref "U$25") (pin "2") (pinfunction "GND_2") (pintype "bidirectional"))
      (node (ref "U$26") (pin "P$2") (pinfunction "C_P$2") (pintype "bidirectional"))
      (node (ref "U$27") (pin "P$2") (pinfunction "C_P$2") (pintype "bidirectional"))
      (node (ref "U$28") (pin "P$2") (pinfunction "C_P$2") (pintype "bidirectional"))
      (node (ref "U$29") (pin "P$2") (pinfunction "C_P$2") (pintype "bidirectional"))
      (node (ref "U$3") (pin "P$2") (pinfunction "C_P$2") (pintype "bidirectional"))
      (node (ref "U$33") (pin "SIDE") (pinfunction "C_SIDE") (pintype "bidirectional"))
      (node (ref "U$34") (pin "SIDE") (pinfunction "C_SIDE") (pintype "bidirectional"))
      (node (ref "U$35") (pin "2") (pinfunction "GND_2") (pintype "bidirectional"))
      (node (ref "U$36") (pin "SIDE") (pinfunction "C_SIDE") (pintype "bidirectional"))
      (node (ref "U$37") (pin "SIDE") (pinfunction "C_SIDE") (pintype "bidirectional"))
      (node (ref "U$38") (pin "SIDE") (pinfunction "C_SIDE") (pintype "bidirectional"))
      (node (ref "U$39") (pin "SIDE") (pinfunction "C_SIDE") (pintype "bidirectional"))
      (node (ref "U$4") (pin "P$2") (pinfunction "C_P$2") (pintype "bidirectional"))
      (node (ref "U$41") (pin "P$2") (pinfunction "C_P$2") (pintype "bidirectional"))
      (node (ref "U$42") (pin "P$2") (pinfunction "C_P$2") (pintype "bidirectional"))
      (node (ref "U$43") (pin "P$2") (pinfunction "C_P$2") (pintype "bidirectional"))
      (node (ref "U$44") (pin "P$2") (pinfunction "C_P$2") (pintype "bidirectional"))
      (node (ref "U$45") (pin "2") (pinfunction "GND_2") (pintype "bidirectional"))
      (node (ref "U$46") (pin "P$2") (pinfunction "C_P$2") (pintype "bidirectional"))
      (node (ref "U$47") (pin "P$2") (pinfunction "C_P$2") (pintype "bidirectional"))
      (node (ref "U$48") (pin "P$2") (pinfunction "C_P$2") (pintype "bidirectional"))
      (node (ref "U$49") (pin "P$2") (pinfunction "C_P$2") (pintype "bidirectional"))
      (node (ref "U$5") (pin "2") (pinfunction "GND_2") (pintype "bidirectional"))
      (node (ref "U$6") (pin "P$2") (pinfunction "C_P$2") (pintype "bidirectional"))
      (node (ref "U$7") (pin "P$2") (pinfunction "C_P$2") (pintype "bidirectional"))
    )
    (net (code "7") (name "Net-(CIN3-Pad1)") (class "Default")
      (node (ref "CIN3") (pin "1") (pinfunction "1_1") (pintype "passive"))
      (node (ref "CIN4") (pin "1") (pinfunction "1_1") (pintype "passive"))
      (node (ref "L2") (pin "1") (pinfunction "1_1") (pintype "passive"))
      (node (ref "R27") (pin "1") (pinfunction "1_1") (pintype "passive"))
      (node (ref "R5") (pin "2") (pinfunction "2_2") (pintype "passive"))
      (node (ref "U$1") (pin "P$1") (pinfunction "A_P$1") (pintype "bidirectional"))
      (node (ref "U$1") (pin "P$10") (pinfunction "A_P$10") (pintype "bidirectional"))
      (node (ref "U$1") (pin "P$11") (pinfunction "A_P$11") (pintype "bidirectional"))
      (node (ref "U$1") (pin "P$12") (pinfunction "A_P$12") (pintype "bidirectional"))
      (node (ref "U$1") (pin "P$13") (pinfunction "A_P$13") (pintype "bidirectional"))
      (node (ref "U$1") (pin "P$14") (pinfunction "A_P$14") (pintype "bidirectional"))
      (node (ref "U$1") (pin "P$15") (pinfunction "A_P$15") (pintype "bidirectional"))
      (node (ref "U$1") (pin "P$16") (pinfunction "A_P$16") (pintype "bidirectional"))
      (node (ref "U$1") (pin "P$3") (pinfunction "A_P$3") (pintype "bidirectional"))
      (node (ref "U$1") (pin "P$4") (pinfunction "A_P$4") (pintype "bidirectional"))
      (node (ref "U$1") (pin "P$5") (pinfunction "A_P$5") (pintype "bidirectional"))
      (node (ref "U$1") (pin "P$6") (pinfunction "A_P$6") (pintype "bidirectional"))
      (node (ref "U$1") (pin "P$7") (pinfunction "A_P$7") (pintype "bidirectional"))
      (node (ref "U$1") (pin "P$8") (pinfunction "A_P$8") (pintype "bidirectional"))
      (node (ref "U$1") (pin "P$9") (pinfunction "A_P$9") (pintype "bidirectional"))
      (node (ref "U$2") (pin "P$1") (pinfunction "A_P$1") (pintype "bidirectional"))
      (node (ref "U$2") (pin "P$10") (pinfunction "A_P$10") (pintype "bidirectional"))
      (node (ref "U$2") (pin "P$11") (pinfunction "A_P$11") (pintype "bidirectional"))
      (node (ref "U$2") (pin "P$12") (pinfunction "A_P$12") (pintype "bidirectional"))
      (node (ref "U$2") (pin "P$13") (pinfunction "A_P$13") (pintype "bidirectional"))
      (node (ref "U$2") (pin "P$14") (pinfunction "A_P$14") (pintype "bidirectional"))
      (node (ref "U$2") (pin "P$15") (pinfunction "A_P$15") (pintype "bidirectional"))
      (node (ref "U$2") (pin "P$16") (pinfunction "A_P$16") (pintype "bidirectional"))
      (node (ref "U$2") (pin "P$3") (pinfunction "A_P$3") (pintype "bidirectional"))
      (node (ref "U$2") (pin "P$4") (pinfunction "A_P$4") (pintype "bidirectional"))
      (node (ref "U$2") (pin "P$5") (pinfunction "A_P$5") (pintype "bidirectional"))
      (node (ref "U$2") (pin "P$6") (pinfunction "A_P$6") (pintype "bidirectional"))
      (node (ref "U$2") (pin "P$7") (pinfunction "A_P$7") (pintype "bidirectional"))
      (node (ref "U$2") (pin "P$8") (pinfunction "A_P$8") (pintype "bidirectional"))
      (node (ref "U$2") (pin "P$9") (pinfunction "A_P$9") (pintype "bidirectional"))
      (node (ref "U$3") (pin "P$1") (pinfunction "A_P$1") (pintype "bidirectional"))
      (node (ref "U$3") (pin "P$10") (pinfunction "A_P$10") (pintype "bidirectional"))
      (node (ref "U$3") (pin "P$11") (pinfunction "A_P$11") (pintype "bidirectional"))
      (node (ref "U$3") (pin "P$12") (pinfunction "A_P$12") (pintype "bidirectional"))
      (node (ref "U$3") (pin "P$13") (pinfunction "A_P$13") (pintype "bidirectional"))
      (node (ref "U$3") (pin "P$14") (pinfunction "A_P$14") (pintype "bidirectional"))
      (node (ref "U$3") (pin "P$15") (pinfunction "A_P$15") (pintype "bidirectional"))
      (node (ref "U$3") (pin "P$16") (pinfunction "A_P$16") (pintype "bidirectional"))
      (node (ref "U$3") (pin "P$3") (pinfunction "A_P$3") (pintype "bidirectional"))
      (node (ref "U$3") (pin "P$4") (pinfunction "A_P$4") (pintype "bidirectional"))
      (node (ref "U$3") (pin "P$5") (pinfunction "A_P$5") (pintype "bidirectional"))
      (node (ref "U$3") (pin "P$6") (pinfunction "A_P$6") (pintype "bidirectional"))
      (node (ref "U$3") (pin "P$7") (pinfunction "A_P$7") (pintype "bidirectional"))
      (node (ref "U$3") (pin "P$8") (pinfunction "A_P$8") (pintype "bidirectional"))
      (node (ref "U$3") (pin "P$9") (pinfunction "A_P$9") (pintype "bidirectional"))
      (node (ref "U$4") (pin "P$1") (pinfunction "A_P$1") (pintype "bidirectional"))
      (node (ref "U$4") (pin "P$10") (pinfunction "A_P$10") (pintype "bidirectional"))
      (node (ref "U$4") (pin "P$11") (pinfunction "A_P$11") (pintype "bidirectional"))
      (node (ref "U$4") (pin "P$12") (pinfunction "A_P$12") (pintype "bidirectional"))
      (node (ref "U$4") (pin "P$13") (pinfunction "A_P$13") (pintype "bidirectional"))
      (node (ref "U$4") (pin "P$14") (pinfunction "A_P$14") (pintype "bidirectional"))
      (node (ref "U$4") (pin "P$15") (pinfunction "A_P$15") (pintype "bidirectional"))
      (node (ref "U$4") (pin "P$16") (pinfunction "A_P$16") (pintype "bidirectional"))
      (node (ref "U$4") (pin "P$3") (pinfunction "A_P$3") (pintype "bidirectional"))
      (node (ref "U$4") (pin "P$4") (pinfunction "A_P$4") (pintype "bidirectional"))
      (node (ref "U$4") (pin "P$5") (pinfunction "A_P$5") (pintype "bidirectional"))
      (node (ref "U$4") (pin "P$6") (pinfunction "A_P$6") (pintype "bidirectional"))
      (node (ref "U$4") (pin "P$7") (pinfunction "A_P$7") (pintype "bidirectional"))
      (node (ref "U$4") (pin "P$8") (pinfunction "A_P$8") (pintype "bidirectional"))
      (node (ref "U$4") (pin "P$9") (pinfunction "A_P$9") (pintype "bidirectional"))
      (node (ref "U$6") (pin "P$1") (pinfunction "A_P$1") (pintype "bidirectional"))
      (node (ref "U$6") (pin "P$10") (pinfunction "A_P$10") (pintype "bidirectional"))
      (node (ref "U$6") (pin "P$11") (pinfunction "A_P$11") (pintype "bidirectional"))
      (node (ref "U$6") (pin "P$12") (pinfunction "A_P$12") (pintype "bidirectional"))
      (node (ref "U$6") (pin "P$13") (pinfunction "A_P$13") (pintype "bidirectional"))
      (node (ref "U$6") (pin "P$14") (pinfunction "A_P$14") (pintype "bidirectional"))
      (node (ref "U$6") (pin "P$15") (pinfunction "A_P$15") (pintype "bidirectional"))
      (node (ref "U$6") (pin "P$16") (pinfunction "A_P$16") (pintype "bidirectional"))
      (node (ref "U$6") (pin "P$3") (pinfunction "A_P$3") (pintype "bidirectional"))
      (node (ref "U$6") (pin "P$4") (pinfunction "A_P$4") (pintype "bidirectional"))
      (node (ref "U$6") (pin "P$5") (pinfunction "A_P$5") (pintype "bidirectional"))
      (node (ref "U$6") (pin "P$6") (pinfunction "A_P$6") (pintype "bidirectional"))
      (node (ref "U$6") (pin "P$7") (pinfunction "A_P$7") (pintype "bidirectional"))
      (node (ref "U$6") (pin "P$8") (pinfunction "A_P$8") (pintype "bidirectional"))
      (node (ref "U$6") (pin "P$9") (pinfunction "A_P$9") (pintype "bidirectional"))
      (node (ref "U$7") (pin "P$1") (pinfunction "A_P$1") (pintype "bidirectional"))
      (node (ref "U$7") (pin "P$10") (pinfunction "A_P$10") (pintype "bidirectional"))
      (node (ref "U$7") (pin "P$11") (pinfunction "A_P$11") (pintype "bidirectional"))
      (node (ref "U$7") (pin "P$12") (pinfunction "A_P$12") (pintype "bidirectional"))
      (node (ref "U$7") (pin "P$13") (pinfunction "A_P$13") (pintype "bidirectional"))
      (node (ref "U$7") (pin "P$14") (pinfunction "A_P$14") (pintype "bidirectional"))
      (node (ref "U$7") (pin "P$15") (pinfunction "A_P$15") (pintype "bidirectional"))
      (node (ref "U$7") (pin "P$16") (pinfunction "A_P$16") (pintype "bidirectional"))
      (node (ref "U$7") (pin "P$3") (pinfunction "A_P$3") (pintype "bidirectional"))
      (node (ref "U$7") (pin "P$4") (pinfunction "A_P$4") (pintype "bidirectional"))
      (node (ref "U$7") (pin "P$5") (pinfunction "A_P$5") (pintype "bidirectional"))
      (node (ref "U$7") (pin "P$6") (pinfunction "A_P$6") (pintype "bidirectional"))
      (node (ref "U$7") (pin "P$7") (pinfunction "A_P$7") (pintype "bidirectional"))
      (node (ref "U$7") (pin "P$8") (pinfunction "A_P$8") (pintype "bidirectional"))
      (node (ref "U$7") (pin "P$9") (pinfunction "A_P$9") (pintype "bidirectional"))
    )
    (net (code "8") (name "Net-(CIN5-Pad1)") (class "Default")
      (node (ref "CIN5") (pin "1") (pinfunction "1_1") (pintype "passive"))
      (node (ref "CIN6") (pin "1") (pinfunction "1_1") (pintype "passive"))
      (node (ref "L3") (pin "1") (pinfunction "1_1") (pintype "passive"))
      (node (ref "R28") (pin "1") (pinfunction "1_1") (pintype "passive"))
      (node (ref "R9") (pin "2") (pinfunction "2_2") (pintype "passive"))
      (node (ref "U$21") (pin "P$1") (pinfunction "A_P$1") (pintype "bidirectional"))
      (node (ref "U$21") (pin "P$10") (pinfunction "A_P$10") (pintype "bidirectional"))
      (node (ref "U$21") (pin "P$11") (pinfunction "A_P$11") (pintype "bidirectional"))
      (node (ref "U$21") (pin "P$12") (pinfunction "A_P$12") (pintype "bidirectional"))
      (node (ref "U$21") (pin "P$13") (pinfunction "A_P$13") (pintype "bidirectional"))
      (node (ref "U$21") (pin "P$14") (pinfunction "A_P$14") (pintype "bidirectional"))
      (node (ref "U$21") (pin "P$15") (pinfunction "A_P$15") (pintype "bidirectional"))
      (node (ref "U$21") (pin "P$16") (pinfunction "A_P$16") (pintype "bidirectional"))
      (node (ref "U$21") (pin "P$3") (pinfunction "A_P$3") (pintype "bidirectional"))
      (node (ref "U$21") (pin "P$4") (pinfunction "A_P$4") (pintype "bidirectional"))
      (node (ref "U$21") (pin "P$5") (pinfunction "A_P$5") (pintype "bidirectional"))
      (node (ref "U$21") (pin "P$6") (pinfunction "A_P$6") (pintype "bidirectional"))
      (node (ref "U$21") (pin "P$7") (pinfunction "A_P$7") (pintype "bidirectional"))
      (node (ref "U$21") (pin "P$8") (pinfunction "A_P$8") (pintype "bidirectional"))
      (node (ref "U$21") (pin "P$9") (pinfunction "A_P$9") (pintype "bidirectional"))
      (node (ref "U$22") (pin "P$1") (pinfunction "A_P$1") (pintype "bidirectional"))
      (node (ref "U$22") (pin "P$10") (pinfunction "A_P$10") (pintype "bidirectional"))
      (node (ref "U$22") (pin "P$11") (pinfunction "A_P$11") (pintype "bidirectional"))
      (node (ref "U$22") (pin "P$12") (pinfunction "A_P$12") (pintype "bidirectional"))
      (node (ref "U$22") (pin "P$13") (pinfunction "A_P$13") (pintype "bidirectional"))
      (node (ref "U$22") (pin "P$14") (pinfunction "A_P$14") (pintype "bidirectional"))
      (node (ref "U$22") (pin "P$15") (pinfunction "A_P$15") (pintype "bidirectional"))
      (node (ref "U$22") (pin "P$16") (pinfunction "A_P$16") (pintype "bidirectional"))
      (node (ref "U$22") (pin "P$3") (pinfunction "A_P$3") (pintype "bidirectional"))
      (node (ref "U$22") (pin "P$4") (pinfunction "A_P$4") (pintype "bidirectional"))
      (node (ref "U$22") (pin "P$5") (pinfunction "A_P$5") (pintype "bidirectional"))
      (node (ref "U$22") (pin "P$6") (pinfunction "A_P$6") (pintype "bidirectional"))
      (node (ref "U$22") (pin "P$7") (pinfunction "A_P$7") (pintype "bidirectional"))
      (node (ref "U$22") (pin "P$8") (pinfunction "A_P$8") (pintype "bidirectional"))
      (node (ref "U$22") (pin "P$9") (pinfunction "A_P$9") (pintype "bidirectional"))
      (node (ref "U$23") (pin "P$1") (pinfunction "A_P$1") (pintype "bidirectional"))
      (node (ref "U$23") (pin "P$10") (pinfunction "A_P$10") (pintype "bidirectional"))
      (node (ref "U$23") (pin "P$11") (pinfunction "A_P$11") (pintype "bidirectional"))
      (node (ref "U$23") (pin "P$12") (pinfunction "A_P$12") (pintype "bidirectional"))
      (node (ref "U$23") (pin "P$13") (pinfunction "A_P$13") (pintype "bidirectional"))
      (node (ref "U$23") (pin "P$14") (pinfunction "A_P$14") (pintype "bidirectional"))
      (node (ref "U$23") (pin "P$15") (pinfunction "A_P$15") (pintype "bidirectional"))
      (node (ref "U$23") (pin "P$16") (pinfunction "A_P$16") (pintype "bidirectional"))
      (node (ref "U$23") (pin "P$3") (pinfunction "A_P$3") (pintype "bidirectional"))
      (node (ref "U$23") (pin "P$4") (pinfunction "A_P$4") (pintype "bidirectional"))
      (node (ref "U$23") (pin "P$5") (pinfunction "A_P$5") (pintype "bidirectional"))
      (node (ref "U$23") (pin "P$6") (pinfunction "A_P$6") (pintype "bidirectional"))
      (node (ref "U$23") (pin "P$7") (pinfunction "A_P$7") (pintype "bidirectional"))
      (node (ref "U$23") (pin "P$8") (pinfunction "A_P$8") (pintype "bidirectional"))
      (node (ref "U$23") (pin "P$9") (pinfunction "A_P$9") (pintype "bidirectional"))
      (node (ref "U$24") (pin "P$1") (pinfunction "A_P$1") (pintype "bidirectional"))
      (node (ref "U$24") (pin "P$10") (pinfunction "A_P$10") (pintype "bidirectional"))
      (node (ref "U$24") (pin "P$11") (pinfunction "A_P$11") (pintype "bidirectional"))
      (node (ref "U$24") (pin "P$12") (pinfunction "A_P$12") (pintype "bidirectional"))
      (node (ref "U$24") (pin "P$13") (pinfunction "A_P$13") (pintype "bidirectional"))
      (node (ref "U$24") (pin "P$14") (pinfunction "A_P$14") (pintype "bidirectional"))
      (node (ref "U$24") (pin "P$15") (pinfunction "A_P$15") (pintype "bidirectional"))
      (node (ref "U$24") (pin "P$16") (pinfunction "A_P$16") (pintype "bidirectional"))
      (node (ref "U$24") (pin "P$3") (pinfunction "A_P$3") (pintype "bidirectional"))
      (node (ref "U$24") (pin "P$4") (pinfunction "A_P$4") (pintype "bidirectional"))
      (node (ref "U$24") (pin "P$5") (pinfunction "A_P$5") (pintype "bidirectional"))
      (node (ref "U$24") (pin "P$6") (pinfunction "A_P$6") (pintype "bidirectional"))
      (node (ref "U$24") (pin "P$7") (pinfunction "A_P$7") (pintype "bidirectional"))
      (node (ref "U$24") (pin "P$8") (pinfunction "A_P$8") (pintype "bidirectional"))
      (node (ref "U$24") (pin "P$9") (pinfunction "A_P$9") (pintype "bidirectional"))
      (node (ref "U$26") (pin "P$1") (pinfunction "A_P$1") (pintype "bidirectional"))
      (node (ref "U$26") (pin "P$10") (pinfunction "A_P$10") (pintype "bidirectional"))
      (node (ref "U$26") (pin "P$11") (pinfunction "A_P$11") (pintype "bidirectional"))
      (node (ref "U$26") (pin "P$12") (pinfunction "A_P$12") (pintype "bidirectional"))
      (node (ref "U$26") (pin "P$13") (pinfunction "A_P$13") (pintype "bidirectional"))
      (node (ref "U$26") (pin "P$14") (pinfunction "A_P$14") (pintype "bidirectional"))
      (node (ref "U$26") (pin "P$15") (pinfunction "A_P$15") (pintype "bidirectional"))
      (node (ref "U$26") (pin "P$16") (pinfunction "A_P$16") (pintype "bidirectional"))
      (node (ref "U$26") (pin "P$3") (pinfunction "A_P$3") (pintype "bidirectional"))
      (node (ref "U$26") (pin "P$4") (pinfunction "A_P$4") (pintype "bidirectional"))
      (node (ref "U$26") (pin "P$5") (pinfunction "A_P$5") (pintype "bidirectional"))
      (node (ref "U$26") (pin "P$6") (pinfunction "A_P$6") (pintype "bidirectional"))
      (node (ref "U$26") (pin "P$7") (pinfunction "A_P$7") (pintype "bidirectional"))
      (node (ref "U$26") (pin "P$8") (pinfunction "A_P$8") (pintype "bidirectional"))
      (node (ref "U$26") (pin "P$9") (pinfunction "A_P$9") (pintype "bidirectional"))
      (node (ref "U$27") (pin "P$1") (pinfunction "A_P$1") (pintype "bidirectional"))
      (node (ref "U$27") (pin "P$10") (pinfunction "A_P$10") (pintype "bidirectional"))
      (node (ref "U$27") (pin "P$11") (pinfunction "A_P$11") (pintype "bidirectional"))
      (node (ref "U$27") (pin "P$12") (pinfunction "A_P$12") (pintype "bidirectional"))
      (node (ref "U$27") (pin "P$13") (pinfunction "A_P$13") (pintype "bidirectional"))
      (node (ref "U$27") (pin "P$14") (pinfunction "A_P$14") (pintype "bidirectional"))
      (node (ref "U$27") (pin "P$15") (pinfunction "A_P$15") (pintype "bidirectional"))
      (node (ref "U$27") (pin "P$16") (pinfunction "A_P$16") (pintype "bidirectional"))
      (node (ref "U$27") (pin "P$3") (pinfunction "A_P$3") (pintype "bidirectional"))
      (node (ref "U$27") (pin "P$4") (pinfunction "A_P$4") (pintype "bidirectional"))
      (node (ref "U$27") (pin "P$5") (pinfunction "A_P$5") (pintype "bidirectional"))
      (node (ref "U$27") (pin "P$6") (pinfunction "A_P$6") (pintype "bidirectional"))
      (node (ref "U$27") (pin "P$7") (pinfunction "A_P$7") (pintype "bidirectional"))
      (node (ref "U$27") (pin "P$8") (pinfunction "A_P$8") (pintype "bidirectional"))
      (node (ref "U$27") (pin "P$9") (pinfunction "A_P$9") (pintype "bidirectional"))
      (node (ref "U$28") (pin "P$1") (pinfunction "A_P$1") (pintype "bidirectional"))
      (node (ref "U$28") (pin "P$10") (pinfunction "A_P$10") (pintype "bidirectional"))
      (node (ref "U$28") (pin "P$11") (pinfunction "A_P$11") (pintype "bidirectional"))
      (node (ref "U$28") (pin "P$12") (pinfunction "A_P$12") (pintype "bidirectional"))
      (node (ref "U$28") (pin "P$13") (pinfunction "A_P$13") (pintype "bidirectional"))
      (node (ref "U$28") (pin "P$14") (pinfunction "A_P$14") (pintype "bidirectional"))
      (node (ref "U$28") (pin "P$15") (pinfunction "A_P$15") (pintype "bidirectional"))
      (node (ref "U$28") (pin "P$16") (pinfunction "A_P$16") (pintype "bidirectional"))
      (node (ref "U$28") (pin "P$3") (pinfunction "A_P$3") (pintype "bidirectional"))
      (node (ref "U$28") (pin "P$4") (pinfunction "A_P$4") (pintype "bidirectional"))
      (node (ref "U$28") (pin "P$5") (pinfunction "A_P$5") (pintype "bidirectional"))
      (node (ref "U$28") (pin "P$6") (pinfunction "A_P$6") (pintype "bidirectional"))
      (node (ref "U$28") (pin "P$7") (pinfunction "A_P$7") (pintype "bidirectional"))
      (node (ref "U$28") (pin "P$8") (pinfunction "A_P$8") (pintype "bidirectional"))
      (node (ref "U$28") (pin "P$9") (pinfunction "A_P$9") (pintype "bidirectional"))
      (node (ref "U$29") (pin "P$1") (pinfunction "A_P$1") (pintype "bidirectional"))
      (node (ref "U$29") (pin "P$10") (pinfunction "A_P$10") (pintype "bidirectional"))
      (node (ref "U$29") (pin "P$11") (pinfunction "A_P$11") (pintype "bidirectional"))
      (node (ref "U$29") (pin "P$12") (pinfunction "A_P$12") (pintype "bidirectional"))
      (node (ref "U$29") (pin "P$13") (pinfunction "A_P$13") (pintype "bidirectional"))
      (node (ref "U$29") (pin "P$14") (pinfunction "A_P$14") (pintype "bidirectional"))
      (node (ref "U$29") (pin "P$15") (pinfunction "A_P$15") (pintype "bidirectional"))
      (node (ref "U$29") (pin "P$16") (pinfunction "A_P$16") (pintype "bidirectional"))
      (node (ref "U$29") (pin "P$3") (pinfunction "A_P$3") (pintype "bidirectional"))
      (node (ref "U$29") (pin "P$4") (pinfunction "A_P$4") (pintype "bidirectional"))
      (node (ref "U$29") (pin "P$5") (pinfunction "A_P$5") (pintype "bidirectional"))
      (node (ref "U$29") (pin "P$6") (pinfunction "A_P$6") (pintype "bidirectional"))
      (node (ref "U$29") (pin "P$7") (pinfunction "A_P$7") (pintype "bidirectional"))
      (node (ref "U$29") (pin "P$8") (pinfunction "A_P$8") (pintype "bidirectional"))
      (node (ref "U$29") (pin "P$9") (pinfunction "A_P$9") (pintype "bidirectional"))
    )
    (net (code "9") (name "Net-(CIN10-Pad1)") (class "Default")
      (node (ref "CIN10") (pin "1") (pinfunction "1_1") (pintype "passive"))
      (node (ref "CIN9") (pin "1") (pinfunction "1_1") (pintype "passive"))
      (node (ref "L5") (pin "1") (pinfunction "1_1") (pintype "passive"))
      (node (ref "R17") (pin "2") (pinfunction "2_2") (pintype "passive"))
      (node (ref "R30") (pin "1") (pinfunction "1_1") (pintype "passive"))
      (node (ref "U$41") (pin "P$1") (pinfunction "A_P$1") (pintype "bidirectional"))
      (node (ref "U$41") (pin "P$10") (pinfunction "A_P$10") (pintype "bidirectional"))
      (node (ref "U$41") (pin "P$11") (pinfunction "A_P$11") (pintype "bidirectional"))
      (node (ref "U$41") (pin "P$12") (pinfunction "A_P$12") (pintype "bidirectional"))
      (node (ref "U$41") (pin "P$13") (pinfunction "A_P$13") (pintype "bidirectional"))
      (node (ref "U$41") (pin "P$14") (pinfunction "A_P$14") (pintype "bidirectional"))
      (node (ref "U$41") (pin "P$15") (pinfunction "A_P$15") (pintype "bidirectional"))
      (node (ref "U$41") (pin "P$16") (pinfunction "A_P$16") (pintype "bidirectional"))
      (node (ref "U$41") (pin "P$3") (pinfunction "A_P$3") (pintype "bidirectional"))
      (node (ref "U$41") (pin "P$4") (pinfunction "A_P$4") (pintype "bidirectional"))
      (node (ref "U$41") (pin "P$5") (pinfunction "A_P$5") (pintype "bidirectional"))
      (node (ref "U$41") (pin "P$6") (pinfunction "A_P$6") (pintype "bidirectional"))
      (node (ref "U$41") (pin "P$7") (pinfunction "A_P$7") (pintype "bidirectional"))
      (node (ref "U$41") (pin "P$8") (pinfunction "A_P$8") (pintype "bidirectional"))
      (node (ref "U$41") (pin "P$9") (pinfunction "A_P$9") (pintype "bidirectional"))
      (node (ref "U$42") (pin "P$1") (pinfunction "A_P$1") (pintype "bidirectional"))
      (node (ref "U$42") (pin "P$10") (pinfunction "A_P$10") (pintype "bidirectional"))
      (node (ref "U$42") (pin "P$11") (pinfunction "A_P$11") (pintype "bidirectional"))
      (node (ref "U$42") (pin "P$12") (pinfunction "A_P$12") (pintype "bidirectional"))
      (node (ref "U$42") (pin "P$13") (pinfunction "A_P$13") (pintype "bidirectional"))
      (node (ref "U$42") (pin "P$14") (pinfunction "A_P$14") (pintype "bidirectional"))
      (node (ref "U$42") (pin "P$15") (pinfunction "A_P$15") (pintype "bidirectional"))
      (node (ref "U$42") (pin "P$16") (pinfunction "A_P$16") (pintype "bidirectional"))
      (node (ref "U$42") (pin "P$3") (pinfunction "A_P$3") (pintype "bidirectional"))
      (node (ref "U$42") (pin "P$4") (pinfunction "A_P$4") (pintype "bidirectional"))
      (node (ref "U$42") (pin "P$5") (pinfunction "A_P$5") (pintype "bidirectional"))
      (node (ref "U$42") (pin "P$6") (pinfunction "A_P$6") (pintype "bidirectional"))
      (node (ref "U$42") (pin "P$7") (pinfunction "A_P$7") (pintype "bidirectional"))
      (node (ref "U$42") (pin "P$8") (pinfunction "A_P$8") (pintype "bidirectional"))
      (node (ref "U$42") (pin "P$9") (pinfunction "A_P$9") (pintype "bidirectional"))
      (node (ref "U$43") (pin "P$1") (pinfunction "A_P$1") (pintype "bidirectional"))
      (node (ref "U$43") (pin "P$10") (pinfunction "A_P$10") (pintype "bidirectional"))
      (node (ref "U$43") (pin "P$11") (pinfunction "A_P$11") (pintype "bidirectional"))
      (node (ref "U$43") (pin "P$12") (pinfunction "A_P$12") (pintype "bidirectional"))
      (node (ref "U$43") (pin "P$13") (pinfunction "A_P$13") (pintype "bidirectional"))
      (node (ref "U$43") (pin "P$14") (pinfunction "A_P$14") (pintype "bidirectional"))
      (node (ref "U$43") (pin "P$15") (pinfunction "A_P$15") (pintype "bidirectional"))
      (node (ref "U$43") (pin "P$16") (pinfunction "A_P$16") (pintype "bidirectional"))
      (node (ref "U$43") (pin "P$3") (pinfunction "A_P$3") (pintype "bidirectional"))
      (node (ref "U$43") (pin "P$4") (pinfunction "A_P$4") (pintype "bidirectional"))
      (node (ref "U$43") (pin "P$5") (pinfunction "A_P$5") (pintype "bidirectional"))
      (node (ref "U$43") (pin "P$6") (pinfunction "A_P$6") (pintype "bidirectional"))
      (node (ref "U$43") (pin "P$7") (pinfunction "A_P$7") (pintype "bidirectional"))
      (node (ref "U$43") (pin "P$8") (pinfunction "A_P$8") (pintype "bidirectional"))
      (node (ref "U$43") (pin "P$9") (pinfunction "A_P$9") (pintype "bidirectional"))
      (node (ref "U$44") (pin "P$1") (pinfunction "A_P$1") (pintype "bidirectional"))
      (node (ref "U$44") (pin "P$10") (pinfunction "A_P$10") (pintype "bidirectional"))
      (node (ref "U$44") (pin "P$11") (pinfunction "A_P$11") (pintype "bidirectional"))
      (node (ref "U$44") (pin "P$12") (pinfunction "A_P$12") (pintype "bidirectional"))
      (node (ref "U$44") (pin "P$13") (pinfunction "A_P$13") (pintype "bidirectional"))
      (node (ref "U$44") (pin "P$14") (pinfunction "A_P$14") (pintype "bidirectional"))
      (node (ref "U$44") (pin "P$15") (pinfunction "A_P$15") (pintype "bidirectional"))
      (node (ref "U$44") (pin "P$16") (pinfunction "A_P$16") (pintype "bidirectional"))
      (node (ref "U$44") (pin "P$3") (pinfunction "A_P$3") (pintype "bidirectional"))
      (node (ref "U$44") (pin "P$4") (pinfunction "A_P$4") (pintype "bidirectional"))
      (node (ref "U$44") (pin "P$5") (pinfunction "A_P$5") (pintype "bidirectional"))
      (node (ref "U$44") (pin "P$6") (pinfunction "A_P$6") (pintype "bidirectional"))
      (node (ref "U$44") (pin "P$7") (pinfunction "A_P$7") (pintype "bidirectional"))
      (node (ref "U$44") (pin "P$8") (pinfunction "A_P$8") (pintype "bidirectional"))
      (node (ref "U$44") (pin "P$9") (pinfunction "A_P$9") (pintype "bidirectional"))
      (node (ref "U$46") (pin "P$1") (pinfunction "A_P$1") (pintype "bidirectional"))
      (node (ref "U$46") (pin "P$10") (pinfunction "A_P$10") (pintype "bidirectional"))
      (node (ref "U$46") (pin "P$11") (pinfunction "A_P$11") (pintype "bidirectional"))
      (node (ref "U$46") (pin "P$12") (pinfunction "A_P$12") (pintype "bidirectional"))
      (node (ref "U$46") (pin "P$13") (pinfunction "A_P$13") (pintype "bidirectional"))
      (node (ref "U$46") (pin "P$14") (pinfunction "A_P$14") (pintype "bidirectional"))
      (node (ref "U$46") (pin "P$15") (pinfunction "A_P$15") (pintype "bidirectional"))
      (node (ref "U$46") (pin "P$16") (pinfunction "A_P$16") (pintype "bidirectional"))
      (node (ref "U$46") (pin "P$3") (pinfunction "A_P$3") (pintype "bidirectional"))
      (node (ref "U$46") (pin "P$4") (pinfunction "A_P$4") (pintype "bidirectional"))
      (node (ref "U$46") (pin "P$5") (pinfunction "A_P$5") (pintype "bidirectional"))
      (node (ref "U$46") (pin "P$6") (pinfunction "A_P$6") (pintype "bidirectional"))
      (node (ref "U$46") (pin "P$7") (pinfunction "A_P$7") (pintype "bidirectional"))
      (node (ref "U$46") (pin "P$8") (pinfunction "A_P$8") (pintype "bidirectional"))
      (node (ref "U$46") (pin "P$9") (pinfunction "A_P$9") (pintype "bidirectional"))
      (node (ref "U$47") (pin "P$1") (pinfunction "A_P$1") (pintype "bidirectional"))
      (node (ref "U$47") (pin "P$10") (pinfunction "A_P$10") (pintype "bidirectional"))
      (node (ref "U$47") (pin "P$11") (pinfunction "A_P$11") (pintype "bidirectional"))
      (node (ref "U$47") (pin "P$12") (pinfunction "A_P$12") (pintype "bidirectional"))
      (node (ref "U$47") (pin "P$13") (pinfunction "A_P$13") (pintype "bidirectional"))
      (node (ref "U$47") (pin "P$14") (pinfunction "A_P$14") (pintype "bidirectional"))
      (node (ref "U$47") (pin "P$15") (pinfunction "A_P$15") (pintype "bidirectional"))
      (node (ref "U$47") (pin "P$16") (pinfunction "A_P$16") (pintype "bidirectional"))
      (node (ref "U$47") (pin "P$3") (pinfunction "A_P$3") (pintype "bidirectional"))
      (node (ref "U$47") (pin "P$4") (pinfunction "A_P$4") (pintype "bidirectional"))
      (node (ref "U$47") (pin "P$5") (pinfunction "A_P$5") (pintype "bidirectional"))
      (node (ref "U$47") (pin "P$6") (pinfunction "A_P$6") (pintype "bidirectional"))
      (node (ref "U$47") (pin "P$7") (pinfunction "A_P$7") (pintype "bidirectional"))
      (node (ref "U$47") (pin "P$8") (pinfunction "A_P$8") (pintype "bidirectional"))
      (node (ref "U$47") (pin "P$9") (pinfunction "A_P$9") (pintype "bidirectional"))
      (node (ref "U$48") (pin "P$1") (pinfunction "A_P$1") (pintype "bidirectional"))
      (node (ref "U$48") (pin "P$10") (pinfunction "A_P$10") (pintype "bidirectional"))
      (node (ref "U$48") (pin "P$11") (pinfunction "A_P$11") (pintype "bidirectional"))
      (node (ref "U$48") (pin "P$12") (pinfunction "A_P$12") (pintype "bidirectional"))
      (node (ref "U$48") (pin "P$13") (pinfunction "A_P$13") (pintype "bidirectional"))
      (node (ref "U$48") (pin "P$14") (pinfunction "A_P$14") (pintype "bidirectional"))
      (node (ref "U$48") (pin "P$15") (pinfunction "A_P$15") (pintype "bidirectional"))
      (node (ref "U$48") (pin "P$16") (pinfunction "A_P$16") (pintype "bidirectional"))
      (node (ref "U$48") (pin "P$3") (pinfunction "A_P$3") (pintype "bidirectional"))
      (node (ref "U$48") (pin "P$4") (pinfunction "A_P$4") (pintype "bidirectional"))
      (node (ref "U$48") (pin "P$5") (pinfunction "A_P$5") (pintype "bidirectional"))
      (node (ref "U$48") (pin "P$6") (pinfunction "A_P$6") (pintype "bidirectional"))
      (node (ref "U$48") (pin "P$7") (pinfunction "A_P$7") (pintype "bidirectional"))
      (node (ref "U$48") (pin "P$8") (pinfunction "A_P$8") (pintype "bidirectional"))
      (node (ref "U$48") (pin "P$9") (pinfunction "A_P$9") (pintype "bidirectional"))
      (node (ref "U$49") (pin "P$1") (pinfunction "A_P$1") (pintype "bidirectional"))
      (node (ref "U$49") (pin "P$10") (pinfunction "A_P$10") (pintype "bidirectional"))
      (node (ref "U$49") (pin "P$11") (pinfunction "A_P$11") (pintype "bidirectional"))
      (node (ref "U$49") (pin "P$12") (pinfunction "A_P$12") (pintype "bidirectional"))
      (node (ref "U$49") (pin "P$13") (pinfunction "A_P$13") (pintype "bidirectional"))
      (node (ref "U$49") (pin "P$14") (pinfunction "A_P$14") (pintype "bidirectional"))
      (node (ref "U$49") (pin "P$15") (pinfunction "A_P$15") (pintype "bidirectional"))
      (node (ref "U$49") (pin "P$16") (pinfunction "A_P$16") (pintype "bidirectional"))
      (node (ref "U$49") (pin "P$3") (pinfunction "A_P$3") (pintype "bidirectional"))
      (node (ref "U$49") (pin "P$4") (pinfunction "A_P$4") (pintype "bidirectional"))
      (node (ref "U$49") (pin "P$5") (pinfunction "A_P$5") (pintype "bidirectional"))
      (node (ref "U$49") (pin "P$6") (pinfunction "A_P$6") (pintype "bidirectional"))
      (node (ref "U$49") (pin "P$7") (pinfunction "A_P$7") (pintype "bidirectional"))
      (node (ref "U$49") (pin "P$8") (pinfunction "A_P$8") (pintype "bidirectional"))
      (node (ref "U$49") (pin "P$9") (pinfunction "A_P$9") (pintype "bidirectional"))
    )
    (net (code "10") (name "Net-(Q6-G)") (class "Default")
      (node (ref "J2") (pin "1") (pinfunction "1_1") (pintype "passive"))
      (node (ref "Q6") (pin "1") (pinfunction "G_1") (pintype "bidirectional"))
      (node (ref "R31") (pin "2") (pinfunction "2_2") (pintype "passive"))
    )
    (net (code "11") (name "Net-(U$5-ICTRL_+)") (class "Default")
      (node (ref "CF2") (pin "1") (pinfunction "1_1") (pintype "passive"))
      (node (ref "RF3") (pin "2") (pinfunction "2_2") (pintype "passive"))
      (node (ref "U$5") (pin "7") (pinfunction "ICTRL_+_7") (pintype "bidirectional"))
    )
    (net (code "12") (name "Net-(U$5-ICTRL_-)") (class "Default")
      (node (ref "CF2") (pin "2") (pinfunction "2_2") (pintype "passive"))
      (node (ref "RF4") (pin "2") (pinfunction "2_2") (pintype "passive"))
      (node (ref "U$5") (pin "6") (pinfunction "ICTRL_-_6") (pintype "bidirectional"))
    )
    (net (code "13") (name "Net-(U$5-LX)") (class "Default")
      (node (ref "L2") (pin "2") (pinfunction "2_2") (pintype "passive"))
      (node (ref "U$5") (pin "3") (pinfunction "LX_3") (pintype "bidirectional"))
    )
    (net (code "14") (name "Net-(U$5-MPPSET)") (class "Default")
      (node (ref "C3") (pin "1") (pinfunction "1_1") (pintype "passive"))
      (node (ref "R5") (pin "1") (pinfunction "1_1") (pintype "passive"))
      (node (ref "U$5") (pin "1") (pinfunction "MPPSET_1") (pintype "bidirectional"))
    )
    (net (code "15") (name "Net-(U$5-VCTRL)") (class "Default")
      (node (ref "C1") (pin "1") (pinfunction "1_1") (pintype "passive"))
      (node (ref "R6") (pin "2") (pinfunction "2_2") (pintype "passive"))
      (node (ref "R7") (pin "1") (pinfunction "1_1") (pintype "passive"))
      (node (ref "U$5") (pin "5") (pinfunction "VCTRL_5") (pintype "bidirectional"))
    )
    (net (code "16") (name "Net-(U$5-VOUT)") (class "Default")
      (node (ref "COUT2") (pin "1") (pinfunction "1_1") (pintype "passive"))
      (node (ref "D2") (pin "C") (pinfunction "C_C") (pintype "passive"))
      (node (ref "RF3") (pin "1") (pinfunction "1_1") (pintype "passive"))
      (node (ref "RS2") (pin "1") (pinfunction "1_1") (pintype "passive"))
      (node (ref "U$5") (pin "4") (pinfunction "VOUT_4") (pintype "bidirectional"))
    )
    (net (code "17") (name "Net-(U$15-ICTRL_+)") (class "Default")
      (node (ref "CF1") (pin "1") (pinfunction "1_1") (pintype "passive"))
      (node (ref "RF1") (pin "2") (pinfunction "2_2") (pintype "passive"))
      (node (ref "U$15") (pin "7") (pinfunction "ICTRL_+_7") (pintype "bidirectional"))
    )
    (net (code "18") (name "Net-(U$15-ICTRL_-)") (class "Default")
      (node (ref "CF1") (pin "2") (pinfunction "2_2") (pintype "passive"))
      (node (ref "RF2") (pin "2") (pinfunction "2_2") (pintype "passive"))
      (node (ref "U$15") (pin "6") (pinfunction "ICTRL_-_6") (pintype "bidirectional"))
    )
    (net (code "19") (name "Net-(U$15-LX)") (class "Default")
      (node (ref "L1") (pin "2") (pinfunction "2_2") (pintype "passive"))
      (node (ref "U$15") (pin "3") (pinfunction "LX_3") (pintype "bidirectional"))
    )
    (net (code "20") (name "Net-(U$15-MPPSET)") (class "Default")
      (node (ref "C4") (pin "1") (pinfunction "1_1") (pintype "passive"))
      (node (ref "R3") (pin "1") (pinfunction "1_1") (pintype "passive"))
      (node (ref "U$15") (pin "1") (pinfunction "MPPSET_1") (pintype "bidirectional"))
    )
    (net (code "21") (name "Net-(U$15-VCTRL)") (class "Default")
      (node (ref "C2") (pin "1") (pinfunction "1_1") (pintype "passive"))
      (node (ref "R1") (pin "2") (pinfunction "2_2") (pintype "passive"))
      (node (ref "R2") (pin "1") (pinfunction "1_1") (pintype "passive"))
      (node (ref "U$15") (pin "5") (pinfunction "VCTRL_5") (pintype "bidirectional"))
    )
    (net (code "22") (name "Net-(U$15-VOUT)") (class "Default")
      (node (ref "COUT1") (pin "1") (pinfunction "1_1") (pintype "passive"))
      (node (ref "D1") (pin "C") (pinfunction "C_C") (pintype "passive"))
      (node (ref "RF1") (pin "1") (pinfunction "1_1") (pintype "passive"))
      (node (ref "RS1") (pin "1") (pinfunction "1_1") (pintype "passive"))
      (node (ref "U$15") (pin "4") (pinfunction "VOUT_4") (pintype "bidirectional"))
    )
    (net (code "23") (name "Net-(U$18-A)") (class "Default")
      (node (ref "CIN1") (pin "1") (pinfunction "1_1") (pintype "passive"))
      (node (ref "CIN2") (pin "1") (pinfunction "1_1") (pintype "passive"))
      (node (ref "L1") (pin "1") (pinfunction "1_1") (pintype "passive"))
      (node (ref "R26") (pin "1") (pinfunction "1_1") (pintype "passive"))
      (node (ref "R3") (pin "2") (pinfunction "2_2") (pintype "passive"))
      (node (ref "U$11") (pin "P$1") (pinfunction "A_P$1") (pintype "bidirectional"))
      (node (ref "U$11") (pin "P$10") (pinfunction "A_P$10") (pintype "bidirectional"))
      (node (ref "U$11") (pin "P$11") (pinfunction "A_P$11") (pintype "bidirectional"))
      (node (ref "U$11") (pin "P$12") (pinfunction "A_P$12") (pintype "bidirectional"))
      (node (ref "U$11") (pin "P$13") (pinfunction "A_P$13") (pintype "bidirectional"))
      (node (ref "U$11") (pin "P$14") (pinfunction "A_P$14") (pintype "bidirectional"))
      (node (ref "U$11") (pin "P$15") (pinfunction "A_P$15") (pintype "bidirectional"))
      (node (ref "U$11") (pin "P$16") (pinfunction "A_P$16") (pintype "bidirectional"))
      (node (ref "U$11") (pin "P$3") (pinfunction "A_P$3") (pintype "bidirectional"))
      (node (ref "U$11") (pin "P$4") (pinfunction "A_P$4") (pintype "bidirectional"))
      (node (ref "U$11") (pin "P$5") (pinfunction "A_P$5") (pintype "bidirectional"))
      (node (ref "U$11") (pin "P$6") (pinfunction "A_P$6") (pintype "bidirectional"))
      (node (ref "U$11") (pin "P$7") (pinfunction "A_P$7") (pintype "bidirectional"))
      (node (ref "U$11") (pin "P$8") (pinfunction "A_P$8") (pintype "bidirectional"))
      (node (ref "U$11") (pin "P$9") (pinfunction "A_P$9") (pintype "bidirectional"))
      (node (ref "U$12") (pin "P$1") (pinfunction "A_P$1") (pintype "bidirectional"))
      (node (ref "U$12") (pin "P$10") (pinfunction "A_P$10") (pintype "bidirectional"))
      (node (ref "U$12") (pin "P$11") (pinfunction "A_P$11") (pintype "bidirectional"))
      (node (ref "U$12") (pin "P$12") (pinfunction "A_P$12") (pintype "bidirectional"))
      (node (ref "U$12") (pin "P$13") (pinfunction "A_P$13") (pintype "bidirectional"))
      (node (ref "U$12") (pin "P$14") (pinfunction "A_P$14") (pintype "bidirectional"))
      (node (ref "U$12") (pin "P$15") (pinfunction "A_P$15") (pintype "bidirectional"))
      (node (ref "U$12") (pin "P$16") (pinfunction "A_P$16") (pintype "bidirectional"))
      (node (ref "U$12") (pin "P$3") (pinfunction "A_P$3") (pintype "bidirectional"))
      (node (ref "U$12") (pin "P$4") (pinfunction "A_P$4") (pintype "bidirectional"))
      (node (ref "U$12") (pin "P$5") (pinfunction "A_P$5") (pintype "bidirectional"))
      (node (ref "U$12") (pin "P$6") (pinfunction "A_P$6") (pintype "bidirectional"))
      (node (ref "U$12") (pin "P$7") (pinfunction "A_P$7") (pintype "bidirectional"))
      (node (ref "U$12") (pin "P$8") (pinfunction "A_P$8") (pintype "bidirectional"))
      (node (ref "U$12") (pin "P$9") (pinfunction "A_P$9") (pintype "bidirectional"))
      (node (ref "U$13") (pin "P$1") (pinfunction "A_P$1") (pintype "bidirectional"))
      (node (ref "U$13") (pin "P$10") (pinfunction "A_P$10") (pintype "bidirectional"))
      (node (ref "U$13") (pin "P$11") (pinfunction "A_P$11") (pintype "bidirectional"))
      (node (ref "U$13") (pin "P$12") (pinfunction "A_P$12") (pintype "bidirectional"))
      (node (ref "U$13") (pin "P$13") (pinfunction "A_P$13") (pintype "bidirectional"))
      (node (ref "U$13") (pin "P$14") (pinfunction "A_P$14") (pintype "bidirectional"))
      (node (ref "U$13") (pin "P$15") (pinfunction "A_P$15") (pintype "bidirectional"))
      (node (ref "U$13") (pin "P$16") (pinfunction "A_P$16") (pintype "bidirectional"))
      (node (ref "U$13") (pin "P$3") (pinfunction "A_P$3") (pintype "bidirectional"))
      (node (ref "U$13") (pin "P$4") (pinfunction "A_P$4") (pintype "bidirectional"))
      (node (ref "U$13") (pin "P$5") (pinfunction "A_P$5") (pintype "bidirectional"))
      (node (ref "U$13") (pin "P$6") (pinfunction "A_P$6") (pintype "bidirectional"))
      (node (ref "U$13") (pin "P$7") (pinfunction "A_P$7") (pintype "bidirectional"))
      (node (ref "U$13") (pin "P$8") (pinfunction "A_P$8") (pintype "bidirectional"))
      (node (ref "U$13") (pin "P$9") (pinfunction "A_P$9") (pintype "bidirectional"))
      (node (ref "U$14") (pin "P$1") (pinfunction "A_P$1") (pintype "bidirectional"))
      (node (ref "U$14") (pin "P$10") (pinfunction "A_P$10") (pintype "bidirectional"))
      (node (ref "U$14") (pin "P$11") (pinfunction "A_P$11") (pintype "bidirectional"))
      (node (ref "U$14") (pin "P$12") (pinfunction "A_P$12") (pintype "bidirectional"))
      (node (ref "U$14") (pin "P$13") (pinfunction "A_P$13") (pintype "bidirectional"))
      (node (ref "U$14") (pin "P$14") (pinfunction "A_P$14") (pintype "bidirectional"))
      (node (ref "U$14") (pin "P$15") (pinfunction "A_P$15") (pintype "bidirectional"))
      (node (ref "U$14") (pin "P$16") (pinfunction "A_P$16") (pintype "bidirectional"))
      (node (ref "U$14") (pin "P$3") (pinfunction "A_P$3") (pintype "bidirectional"))
      (node (ref "U$14") (pin "P$4") (pinfunction "A_P$4") (pintype "bidirectional"))
      (node (ref "U$14") (pin "P$5") (pinfunction "A_P$5") (pintype "bidirectional"))
      (node (ref "U$14") (pin "P$6") (pinfunction "A_P$6") (pintype "bidirectional"))
      (node (ref "U$14") (pin "P$7") (pinfunction "A_P$7") (pintype "bidirectional"))
      (node (ref "U$14") (pin "P$8") (pinfunction "A_P$8") (pintype "bidirectional"))
      (node (ref "U$14") (pin "P$9") (pinfunction "A_P$9") (pintype "bidirectional"))
      (node (ref "U$16") (pin "P$1") (pinfunction "A_P$1") (pintype "bidirectional"))
      (node (ref "U$16") (pin "P$10") (pinfunction "A_P$10") (pintype "bidirectional"))
      (node (ref "U$16") (pin "P$11") (pinfunction "A_P$11") (pintype "bidirectional"))
      (node (ref "U$16") (pin "P$12") (pinfunction "A_P$12") (pintype "bidirectional"))
      (node (ref "U$16") (pin "P$13") (pinfunction "A_P$13") (pintype "bidirectional"))
      (node (ref "U$16") (pin "P$14") (pinfunction "A_P$14") (pintype "bidirectional"))
      (node (ref "U$16") (pin "P$15") (pinfunction "A_P$15") (pintype "bidirectional"))
      (node (ref "U$16") (pin "P$16") (pinfunction "A_P$16") (pintype "bidirectional"))
      (node (ref "U$16") (pin "P$3") (pinfunction "A_P$3") (pintype "bidirectional"))
      (node (ref "U$16") (pin "P$4") (pinfunction "A_P$4") (pintype "bidirectional"))
      (node (ref "U$16") (pin "P$5") (pinfunction "A_P$5") (pintype "bidirectional"))
      (node (ref "U$16") (pin "P$6") (pinfunction "A_P$6") (pintype "bidirectional"))
      (node (ref "U$16") (pin "P$7") (pinfunction "A_P$7") (pintype "bidirectional"))
      (node (ref "U$16") (pin "P$8") (pinfunction "A_P$8") (pintype "bidirectional"))
      (node (ref "U$16") (pin "P$9") (pinfunction "A_P$9") (pintype "bidirectional"))
      (node (ref "U$17") (pin "P$1") (pinfunction "A_P$1") (pintype "bidirectional"))
      (node (ref "U$17") (pin "P$10") (pinfunction "A_P$10") (pintype "bidirectional"))
      (node (ref "U$17") (pin "P$11") (pinfunction "A_P$11") (pintype "bidirectional"))
      (node (ref "U$17") (pin "P$12") (pinfunction "A_P$12") (pintype "bidirectional"))
      (node (ref "U$17") (pin "P$13") (pinfunction "A_P$13") (pintype "bidirectional"))
      (node (ref "U$17") (pin "P$14") (pinfunction "A_P$14") (pintype "bidirectional"))
      (node (ref "U$17") (pin "P$15") (pinfunction "A_P$15") (pintype "bidirectional"))
      (node (ref "U$17") (pin "P$16") (pinfunction "A_P$16") (pintype "bidirectional"))
      (node (ref "U$17") (pin "P$3") (pinfunction "A_P$3") (pintype "bidirectional"))
      (node (ref "U$17") (pin "P$4") (pinfunction "A_P$4") (pintype "bidirectional"))
      (node (ref "U$17") (pin "P$5") (pinfunction "A_P$5") (pintype "bidirectional"))
      (node (ref "U$17") (pin "P$6") (pinfunction "A_P$6") (pintype "bidirectional"))
      (node (ref "U$17") (pin "P$7") (pinfunction "A_P$7") (pintype "bidirectional"))
      (node (ref "U$17") (pin "P$8") (pinfunction "A_P$8") (pintype "bidirectional"))
      (node (ref "U$17") (pin "P$9") (pinfunction "A_P$9") (pintype "bidirectional"))
      (node (ref "U$18") (pin "P$2") (pinfunction "A_P$2") (pintype "bidirectional"))
      (node (ref "U$19") (pin "P$2") (pinfunction "A_P$2") (pintype "bidirectional"))
    )
    (net (code "24") (name "Net-(U$25-ICTRL_+)") (class "Default")
      (node (ref "CF3") (pin "1") (pinfunction "1_1") (pintype "passive"))
      (node (ref "RF5") (pin "2") (pinfunction "2_2") (pintype "passive"))
      (node (ref "U$25") (pin "7") (pinfunction "ICTRL_+_7") (pintype "bidirectional"))
    )
    (net (code "25") (name "Net-(U$25-ICTRL_-)") (class "Default")
      (node (ref "CF3") (pin "2") (pinfunction "2_2") (pintype "passive"))
      (node (ref "RF6") (pin "2") (pinfunction "2_2") (pintype "passive"))
      (node (ref "U$25") (pin "6") (pinfunction "ICTRL_-_6") (pintype "bidirectional"))
    )
    (net (code "26") (name "Net-(U$25-LX)") (class "Default")
      (node (ref "L3") (pin "2") (pinfunction "2_2") (pintype "passive"))
      (node (ref "U$25") (pin "3") (pinfunction "LX_3") (pintype "bidirectional"))
    )
    (net (code "27") (name "Net-(U$25-MPPSET)") (class "Default")
      (node (ref "C6") (pin "1") (pinfunction "1_1") (pintype "passive"))
      (node (ref "R9") (pin "1") (pinfunction "1_1") (pintype "passive"))
      (node (ref "U$25") (pin "1") (pinfunction "MPPSET_1") (pintype "bidirectional"))
    )
    (net (code "28") (name "Net-(U$25-VCTRL)") (class "Default")
      (node (ref "C5") (pin "1") (pinfunction "1_1") (pintype "passive"))
      (node (ref "R10") (pin "2") (pinfunction "2_2") (pintype "passive"))
      (node (ref "R11") (pin "1") (pinfunction "1_1") (pintype "passive"))
      (node (ref "U$25") (pin "5") (pinfunction "VCTRL_5") (pintype "bidirectional"))
    )
    (net (code "29") (name "Net-(U$25-VOUT)") (class "Default")
      (node (ref "COUT3") (pin "1") (pinfunction "1_1") (pintype "passive"))
      (node (ref "D3") (pin "C") (pinfunction "C_C") (pintype "passive"))
      (node (ref "RF5") (pin "1") (pinfunction "1_1") (pintype "passive"))
      (node (ref "RS3") (pin "1") (pinfunction "1_1") (pintype "passive"))
      (node (ref "U$25") (pin "4") (pinfunction "VOUT_4") (pintype "bidirectional"))
    )
    (net (code "30") (name "Net-(U$33-A)") (class "Default")
      (node (ref "CIN7") (pin "1") (pinfunction "1_1") (pintype "passive"))
      (node (ref "CIN8") (pin "1") (pinfunction "1_1") (pintype "passive"))
      (node (ref "L4") (pin "1") (pinfunction "1_1") (pintype "passive"))
      (node (ref "R13") (pin "2") (pinfunction "2_2") (pintype "passive"))
      (node (ref "R29") (pin "1") (pinfunction "1_1") (pintype "passive"))
      (node (ref "U$33") (pin "P$2") (pinfunction "A_P$2") (pintype "bidirectional"))
      (node (ref "U$34") (pin "P$2") (pinfunction "A_P$2") (pintype "bidirectional"))
      (node (ref "U$36") (pin "P$2") (pinfunction "A_P$2") (pintype "bidirectional"))
      (node (ref "U$37") (pin "P$2") (pinfunction "A_P$2") (pintype "bidirectional"))
      (node (ref "U$38") (pin "P$2") (pinfunction "A_P$2") (pintype "bidirectional"))
      (node (ref "U$39") (pin "P$2") (pinfunction "A_P$2") (pintype "bidirectional"))
    )
    (net (code "31") (name "Net-(U$35-ICTRL_+)") (class "Default")
      (node (ref "CF4") (pin "1") (pinfunction "1_1") (pintype "passive"))
      (node (ref "RF7") (pin "2") (pinfunction "2_2") (pintype "passive"))
      (node (ref "U$35") (pin "7") (pinfunction "ICTRL_+_7") (pintype "bidirectional"))
    )
    (net (code "32") (name "Net-(U$35-ICTRL_-)") (class "Default")
      (node (ref "CF4") (pin "2") (pinfunction "2_2") (pintype "passive"))
      (node (ref "RF8") (pin "2") (pinfunction "2_2") (pintype "passive"))
      (node (ref "U$35") (pin "6") (pinfunction "ICTRL_-_6") (pintype "bidirectional"))
    )
    (net (code "33") (name "Net-(U$35-LX)") (class "Default")
      (node (ref "L4") (pin "2") (pinfunction "2_2") (pintype "passive"))
      (node (ref "U$35") (pin "3") (pinfunction "LX_3") (pintype "bidirectional"))
    )
    (net (code "34") (name "Net-(U$35-MPPSET)") (class "Default")
      (node (ref "C8") (pin "1") (pinfunction "1_1") (pintype "passive"))
      (node (ref "R13") (pin "1") (pinfunction "1_1") (pintype "passive"))
      (node (ref "U$35") (pin "1") (pinfunction "MPPSET_1") (pintype "bidirectional"))
    )
    (net (code "35") (name "Net-(U$35-VCTRL)") (class "Default")
      (node (ref "C7") (pin "1") (pinfunction "1_1") (pintype "passive"))
      (node (ref "R14") (pin "2") (pinfunction "2_2") (pintype "passive"))
      (node (ref "R15") (pin "1") (pinfunction "1_1") (pintype "passive"))
      (node (ref "U$35") (pin "5") (pinfunction "VCTRL_5") (pintype "bidirectional"))
    )
    (net (code "36") (name "Net-(U$35-VOUT)") (class "Default")
      (node (ref "COUT4") (pin "1") (pinfunction "1_1") (pintype "passive"))
      (node (ref "D4") (pin "C") (pinfunction "C_C") (pintype "passive"))
      (node (ref "RF7") (pin "1") (pinfunction "1_1") (pintype "passive"))
      (node (ref "RS4") (pin "1") (pinfunction "1_1") (pintype "passive"))
      (node (ref "U$35") (pin "4") (pinfunction "VOUT_4") (pintype "bidirectional"))
    )
    (net (code "37") (name "Net-(U$45-ICTRL_+)") (class "Default")
      (node (ref "CF5") (pin "1") (pinfunction "1_1") (pintype "passive"))
      (node (ref "RF9") (pin "2") (pinfunction "2_2") (pintype "passive"))
      (node (ref "U$45") (pin "7") (pinfunction "ICTRL_+_7") (pintype "bidirectional"))
    )
    (net (code "38") (name "Net-(U$45-ICTRL_-)") (class "Default")
      (node (ref "CF5") (pin "2") (pinfunction "2_2") (pintype "passive"))
      (node (ref "RF10") (pin "2") (pinfunction "2_2") (pintype "passive"))
      (node (ref "U$45") (pin "6") (pinfunction "ICTRL_-_6") (pintype "bidirectional"))
    )
    (net (code "39") (name "Net-(U$45-LX)") (class "Default")
      (node (ref "L5") (pin "2") (pinfunction "2_2") (pintype "passive"))
      (node (ref "U$45") (pin "3") (pinfunction "LX_3") (pintype "bidirectional"))
    )
    (net (code "40") (name "Net-(U$45-MPPSET)") (class "Default")
      (node (ref "C10") (pin "1") (pinfunction "1_1") (pintype "passive"))
      (node (ref "R17") (pin "1") (pinfunction "1_1") (pintype "passive"))
      (node (ref "U$45") (pin "1") (pinfunction "MPPSET_1") (pintype "bidirectional"))
    )
    (net (code "41") (name "Net-(U$45-VCTRL)") (class "Default")
      (node (ref "C9") (pin "1") (pinfunction "1_1") (pintype "passive"))
      (node (ref "R18") (pin "2") (pinfunction "2_2") (pintype "passive"))
      (node (ref "R19") (pin "1") (pinfunction "1_1") (pintype "passive"))
      (node (ref "U$45") (pin "5") (pinfunction "VCTRL_5") (pintype "bidirectional"))
    )
    (net (code "42") (name "Net-(U$45-VOUT)") (class "Default")
      (node (ref "COUT5") (pin "1") (pinfunction "1_1") (pintype "passive"))
      (node (ref "D5") (pin "C") (pinfunction "C_C") (pintype "passive"))
      (node (ref "RF9") (pin "1") (pinfunction "1_1") (pintype "passive"))
      (node (ref "RS5") (pin "1") (pinfunction "1_1") (pintype "passive"))
      (node (ref "U$45") (pin "4") (pinfunction "VOUT_4") (pintype "bidirectional"))
    )
    (net (code "43") (name "POUT") (class "Default")
      (node (ref "D10") (pin "C") (pinfunction "C_C") (pintype "passive"))
      (node (ref "D6") (pin "C") (pinfunction "C_C") (pintype "passive"))
      (node (ref "D7") (pin "C") (pinfunction "C_C") (pintype "passive"))
      (node (ref "D8") (pin "C") (pinfunction "C_C") (pintype "passive"))
      (node (ref "D9") (pin "C") (pinfunction "C_C") (pintype "passive"))
      (node (ref "J1") (pin "1") (pinfunction "1_1") (pintype "passive"))
      (node (ref "R32") (pin "2") (pinfunction "2_2") (pintype "passive"))
    )
    (net (code "44") (name "XCTRL") (class "Default")
      (node (ref "Q6") (pin "3") (pinfunction "D_3") (pintype "bidirectional"))
      (node (ref "R26") (pin "2") (pinfunction "2_2") (pintype "passive"))
      (node (ref "R27") (pin "2") (pinfunction "2_2") (pintype "passive"))
      (node (ref "R28") (pin "2") (pinfunction "2_2") (pintype "passive"))
      (node (ref "R29") (pin "2") (pinfunction "2_2") (pintype "passive"))
      (node (ref "R30") (pin "2") (pinfunction "2_2") (pintype "passive"))
      (node (ref "R32") (pin "1") (pinfunction "1_1") (pintype "passive"))
      (node (ref "U$15") (pin "8") (pinfunction "XSHUT_8") (pintype "bidirectional"))
      (node (ref "U$25") (pin "8") (pinfunction "XSHUT_8") (pintype "bidirectional"))
      (node (ref "U$35") (pin "8") (pinfunction "XSHUT_8") (pintype "bidirectional"))
      (node (ref "U$45") (pin "8") (pinfunction "XSHUT_8") (pintype "bidirectional"))
      (node (ref "U$5") (pin "8") (pinfunction "XSHUT_8") (pintype "bidirectional"))
    )
  )
)
